# slimarm_apricot-r_b_v1r3.net
KiCad netlist of a schematic drawn in EasyEDA Pro
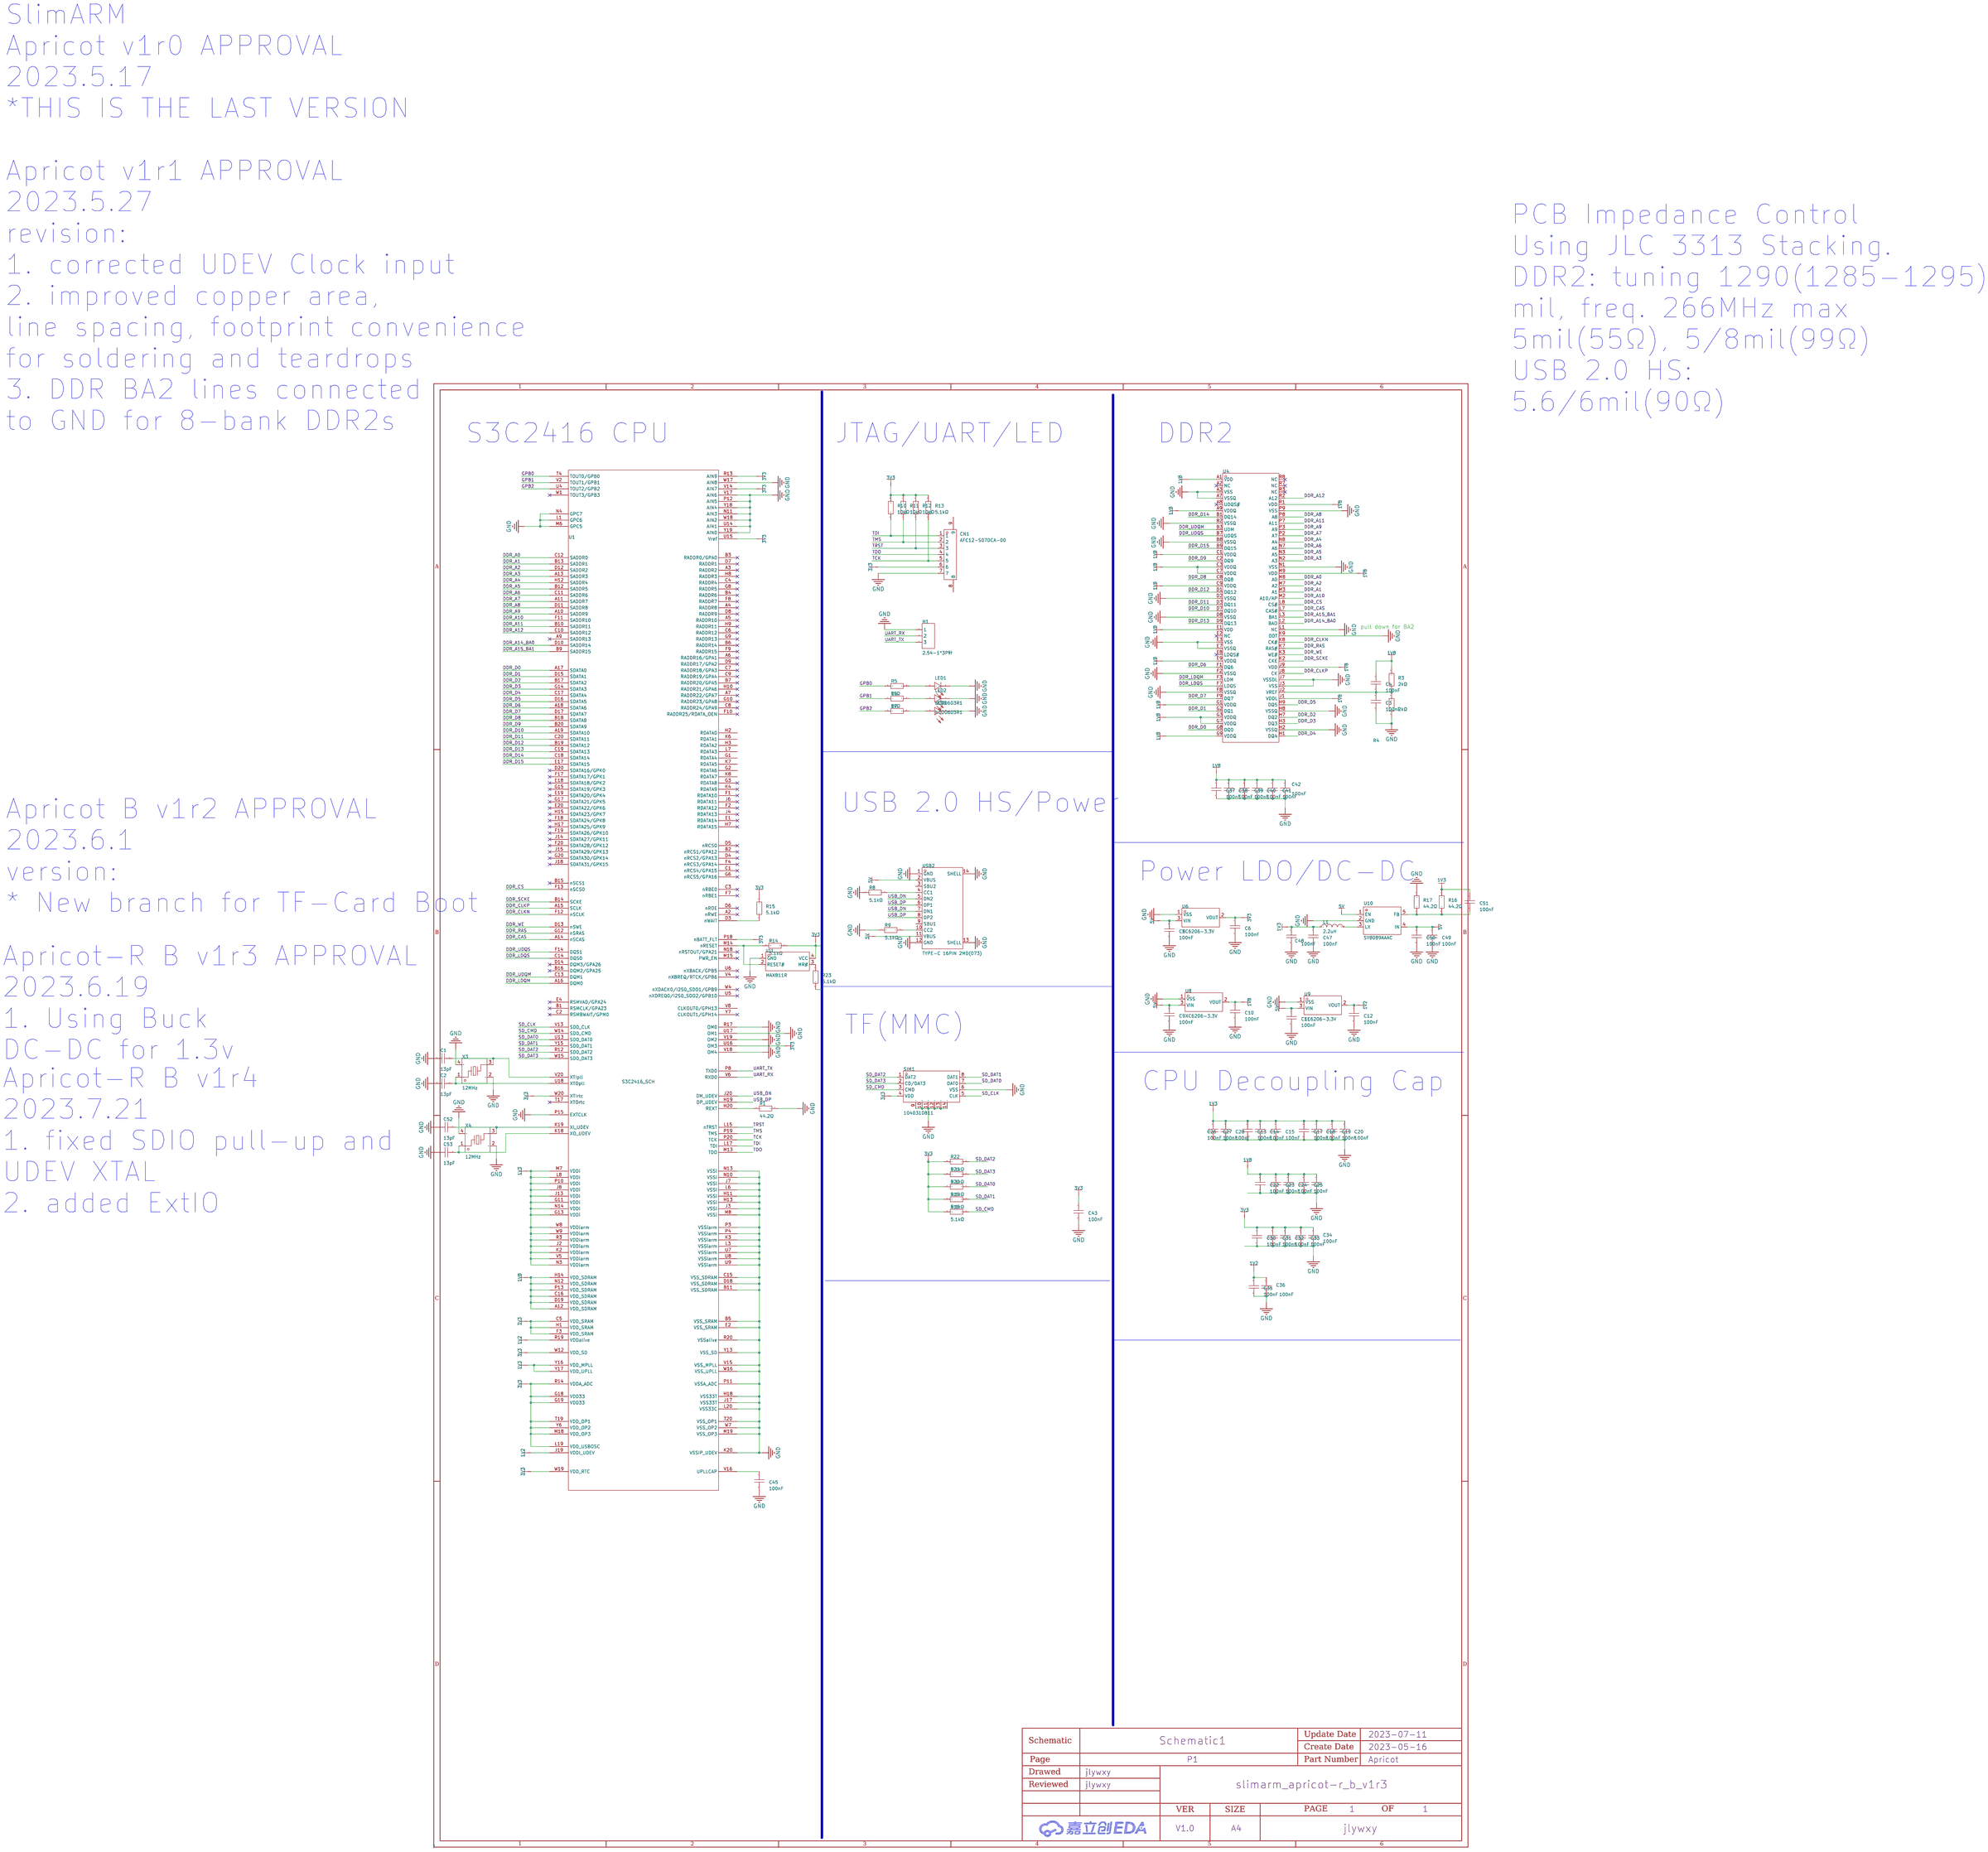
[diagram p0: schematic sheet]

(export (version "E")
  (design (tool "Eeschema 10.0.6"))
  (components
    (comp (ref "C1")
      (value "13pF")
      (footprint "easyedapro:C0402")
      (description "容值:22pF;精度:±5%;额定电压:50V;材质(温度系数):NP0;")
      (fields
        (field (name "Manufacturer Part") "CC0402JRNPO9BN220")
        (field (name "Manufacturer") "YAGEO(国巨)")
      )
      (libsource (lib "easyedapro") (part "CC0402JRNPO9BN220"))
    )
    (comp (ref "C2")
      (value "13pF")
      (footprint "easyedapro:C0402")
      (description "容值:22pF;精度:±5%;额定电压:50V;材质(温度系数):NP0;")
      (fields
        (field (name "Manufacturer Part") "CC0402JRNPO9BN220")
        (field (name "Manufacturer") "YAGEO(国巨)")
      )
      (libsource (lib "easyedapro") (part "CC0402JRNPO9BN220"))
    )
    (comp (ref "C3")
      (value "100nF")
      (footprint "easyedapro:C0402")
      (description "容值:22pF;精度:±5%;额定电压:50V;材质(温度系数):NP0;")
      (fields
        (field (name "Manufacturer Part") "CC0402JRNPO9BN220")
        (field (name "Manufacturer") "YAGEO(国巨)")
      )
      (libsource (lib "easyedapro") (part "CC0402JRNPO9BN220"))
    )
    (comp (ref "C4")
      (value "100nF")
      (footprint "easyedapro:C0402")
      (description "容值:22pF;精度:±5%;额定电压:50V;材质(温度系数):NP0;")
      (fields
        (field (name "Manufacturer Part") "CC0402JRNPO9BN220")
        (field (name "Manufacturer") "YAGEO(国巨)")
      )
      (libsource (lib "easyedapro") (part "CC0402JRNPO9BN220"))
    )
    (comp (ref "C5")
      (value "100nF")
      (footprint "easyedapro:C0402")
      (description "容值:22pF;精度:±5%;额定电压:50V;材质(温度系数):NP0;")
      (fields
        (field (name "Manufacturer Part") "CC0402JRNPO9BN220")
        (field (name "Manufacturer") "YAGEO(国巨)")
      )
      (libsource (lib "easyedapro") (part "CC0402JRNPO9BN220"))
    )
    (comp (ref "C6")
      (value "100nF")
      (footprint "easyedapro:C0402")
      (description "容值:22pF;精度:±5%;额定电压:50V;材质(温度系数):NP0;")
      (fields
        (field (name "Manufacturer Part") "CC0402JRNPO9BN220")
        (field (name "Manufacturer") "YAGEO(国巨)")
      )
      (libsource (lib "easyedapro") (part "CC0402JRNPO9BN220"))
    )
    (comp (ref "C9")
      (value "100nF")
      (footprint "easyedapro:C0402")
      (description "容值:22pF;精度:±5%;额定电压:50V;材质(温度系数):NP0;")
      (fields
        (field (name "Manufacturer Part") "CC0402JRNPO9BN220")
        (field (name "Manufacturer") "YAGEO(国巨)")
      )
      (libsource (lib "easyedapro") (part "CC0402JRNPO9BN220"))
    )
    (comp (ref "C10")
      (value "100nF")
      (footprint "easyedapro:C0402")
      (description "容值:22pF;精度:±5%;额定电压:50V;材质(温度系数):NP0;")
      (fields
        (field (name "Manufacturer Part") "CC0402JRNPO9BN220")
        (field (name "Manufacturer") "YAGEO(国巨)")
      )
      (libsource (lib "easyedapro") (part "CC0402JRNPO9BN220"))
    )
    (comp (ref "C11")
      (value "100nF")
      (footprint "easyedapro:C0402")
      (description "容值:22pF;精度:±5%;额定电压:50V;材质(温度系数):NP0;")
      (fields
        (field (name "Manufacturer Part") "CC0402JRNPO9BN220")
        (field (name "Manufacturer") "YAGEO(国巨)")
      )
      (libsource (lib "easyedapro") (part "CC0402JRNPO9BN220"))
    )
    (comp (ref "C12")
      (value "100nF")
      (footprint "easyedapro:C0402")
      (description "容值:22pF;精度:±5%;额定电压:50V;材质(温度系数):NP0;")
      (fields
        (field (name "Manufacturer Part") "CC0402JRNPO9BN220")
        (field (name "Manufacturer") "YAGEO(国巨)")
      )
      (libsource (lib "easyedapro") (part "CC0402JRNPO9BN220"))
    )
    (comp (ref "C13")
      (value "100nF")
      (footprint "easyedapro:C0402")
      (description "容值:22pF;精度:±5%;额定电压:50V;材质(温度系数):NP0;")
      (fields
        (field (name "Manufacturer Part") "CC0402JRNPO9BN220")
        (field (name "Manufacturer") "YAGEO(国巨)")
      )
      (libsource (lib "easyedapro") (part "CC0402JRNPO9BN220"))
    )
    (comp (ref "C14")
      (value "100nF")
      (footprint "easyedapro:C0402")
      (description "容值:22pF;精度:±5%;额定电压:50V;材质(温度系数):NP0;")
      (fields
        (field (name "Manufacturer Part") "CC0402JRNPO9BN220")
        (field (name "Manufacturer") "YAGEO(国巨)")
      )
      (libsource (lib "easyedapro") (part "CC0402JRNPO9BN220"))
    )
    (comp (ref "C15")
      (value "100nF")
      (footprint "easyedapro:C0402")
      (description "容值:22pF;精度:±5%;额定电压:50V;材质(温度系数):NP0;")
      (fields
        (field (name "Manufacturer Part") "CC0402JRNPO9BN220")
        (field (name "Manufacturer") "YAGEO(国巨)")
      )
      (libsource (lib "easyedapro") (part "CC0402JRNPO9BN220"))
    )
    (comp (ref "C17")
      (value "100nF")
      (footprint "easyedapro:C0402")
      (description "容值:22pF;精度:±5%;额定电压:50V;材质(温度系数):NP0;")
      (fields
        (field (name "Manufacturer Part") "CC0402JRNPO9BN220")
        (field (name "Manufacturer") "YAGEO(国巨)")
      )
      (libsource (lib "easyedapro") (part "CC0402JRNPO9BN220"))
    )
    (comp (ref "C18")
      (value "100nF")
      (footprint "easyedapro:C0402")
      (description "容值:22pF;精度:±5%;额定电压:50V;材质(温度系数):NP0;")
      (fields
        (field (name "Manufacturer Part") "CC0402JRNPO9BN220")
        (field (name "Manufacturer") "YAGEO(国巨)")
      )
      (libsource (lib "easyedapro") (part "CC0402JRNPO9BN220"))
    )
    (comp (ref "C19")
      (value "100nF")
      (footprint "easyedapro:C0402")
      (description "容值:22pF;精度:±5%;额定电压:50V;材质(温度系数):NP0;")
      (fields
        (field (name "Manufacturer Part") "CC0402JRNPO9BN220")
        (field (name "Manufacturer") "YAGEO(国巨)")
      )
      (libsource (lib "easyedapro") (part "CC0402JRNPO9BN220"))
    )
    (comp (ref "C20")
      (value "100nF")
      (footprint "easyedapro:C0402")
      (description "容值:22pF;精度:±5%;额定电压:50V;材质(温度系数):NP0;")
      (fields
        (field (name "Manufacturer Part") "CC0402JRNPO9BN220")
        (field (name "Manufacturer") "YAGEO(国巨)")
      )
      (libsource (lib "easyedapro") (part "CC0402JRNPO9BN220"))
    )
    (comp (ref "C22")
      (value "100nF")
      (footprint "easyedapro:C0402")
      (description "容值:22pF;精度:±5%;额定电压:50V;材质(温度系数):NP0;")
      (fields
        (field (name "Manufacturer Part") "CC0402JRNPO9BN220")
        (field (name "Manufacturer") "YAGEO(国巨)")
      )
      (libsource (lib "easyedapro") (part "CC0402JRNPO9BN220"))
    )
    (comp (ref "C23")
      (value "100nF")
      (footprint "easyedapro:C0402")
      (description "容值:22pF;精度:±5%;额定电压:50V;材质(温度系数):NP0;")
      (fields
        (field (name "Manufacturer Part") "CC0402JRNPO9BN220")
        (field (name "Manufacturer") "YAGEO(国巨)")
      )
      (libsource (lib "easyedapro") (part "CC0402JRNPO9BN220"))
    )
    (comp (ref "C24")
      (value "100nF")
      (footprint "easyedapro:C0402")
      (description "容值:22pF;精度:±5%;额定电压:50V;材质(温度系数):NP0;")
      (fields
        (field (name "Manufacturer Part") "CC0402JRNPO9BN220")
        (field (name "Manufacturer") "YAGEO(国巨)")
      )
      (libsource (lib "easyedapro") (part "CC0402JRNPO9BN220"))
    )
    (comp (ref "C25")
      (value "100nF")
      (footprint "easyedapro:C0402")
      (description "容值:22pF;精度:±5%;额定电压:50V;材质(温度系数):NP0;")
      (fields
        (field (name "Manufacturer Part") "CC0402JRNPO9BN220")
        (field (name "Manufacturer") "YAGEO(国巨)")
      )
      (libsource (lib "easyedapro") (part "CC0402JRNPO9BN220"))
    )
    (comp (ref "C26")
      (value "100nF")
      (footprint "easyedapro:C0402")
      (description "容值:22pF;精度:±5%;额定电压:50V;材质(温度系数):NP0;")
      (fields
        (field (name "Manufacturer Part") "CC0402JRNPO9BN220")
        (field (name "Manufacturer") "YAGEO(国巨)")
      )
      (libsource (lib "easyedapro") (part "CC0402JRNPO9BN220"))
    )
    (comp (ref "C27")
      (value "100nF")
      (footprint "easyedapro:C0402")
      (description "容值:22pF;精度:±5%;额定电压:50V;材质(温度系数):NP0;")
      (fields
        (field (name "Manufacturer Part") "CC0402JRNPO9BN220")
        (field (name "Manufacturer") "YAGEO(国巨)")
      )
      (libsource (lib "easyedapro") (part "CC0402JRNPO9BN220"))
    )
    (comp (ref "C28")
      (value "100nF")
      (footprint "easyedapro:C0402")
      (description "容值:22pF;精度:±5%;额定电压:50V;材质(温度系数):NP0;")
      (fields
        (field (name "Manufacturer Part") "CC0402JRNPO9BN220")
        (field (name "Manufacturer") "YAGEO(国巨)")
      )
      (libsource (lib "easyedapro") (part "CC0402JRNPO9BN220"))
    )
    (comp (ref "C30")
      (value "100nF")
      (footprint "easyedapro:C0402")
      (description "容值:22pF;精度:±5%;额定电压:50V;材质(温度系数):NP0;")
      (fields
        (field (name "Manufacturer Part") "CC0402JRNPO9BN220")
        (field (name "Manufacturer") "YAGEO(国巨)")
      )
      (libsource (lib "easyedapro") (part "CC0402JRNPO9BN220"))
    )
    (comp (ref "C31")
      (value "100nF")
      (footprint "easyedapro:C0402")
      (description "容值:22pF;精度:±5%;额定电压:50V;材质(温度系数):NP0;")
      (fields
        (field (name "Manufacturer Part") "CC0402JRNPO9BN220")
        (field (name "Manufacturer") "YAGEO(国巨)")
      )
      (libsource (lib "easyedapro") (part "CC0402JRNPO9BN220"))
    )
    (comp (ref "C32")
      (value "100nF")
      (footprint "easyedapro:C0402")
      (description "容值:22pF;精度:±5%;额定电压:50V;材质(温度系数):NP0;")
      (fields
        (field (name "Manufacturer Part") "CC0402JRNPO9BN220")
        (field (name "Manufacturer") "YAGEO(国巨)")
      )
      (libsource (lib "easyedapro") (part "CC0402JRNPO9BN220"))
    )
    (comp (ref "C33")
      (value "100nF")
      (footprint "easyedapro:C0402")
      (description "容值:22pF;精度:±5%;额定电压:50V;材质(温度系数):NP0;")
      (fields
        (field (name "Manufacturer Part") "CC0402JRNPO9BN220")
        (field (name "Manufacturer") "YAGEO(国巨)")
      )
      (libsource (lib "easyedapro") (part "CC0402JRNPO9BN220"))
    )
    (comp (ref "C34")
      (value "100nF")
      (footprint "easyedapro:C0402")
      (description "容值:22pF;精度:±5%;额定电压:50V;材质(温度系数):NP0;")
      (fields
        (field (name "Manufacturer Part") "CC0402JRNPO9BN220")
        (field (name "Manufacturer") "YAGEO(国巨)")
      )
      (libsource (lib "easyedapro") (part "CC0402JRNPO9BN220"))
    )
    (comp (ref "C35")
      (value "100nF")
      (footprint "easyedapro:C0402")
      (description "容值:22pF;精度:±5%;额定电压:50V;材质(温度系数):NP0;")
      (fields
        (field (name "Manufacturer Part") "CC0402JRNPO9BN220")
        (field (name "Manufacturer") "YAGEO(国巨)")
      )
      (libsource (lib "easyedapro") (part "CC0402JRNPO9BN220"))
    )
    (comp (ref "C36")
      (value "100nF")
      (footprint "easyedapro:C0402")
      (description "容值:22pF;精度:±5%;额定电压:50V;材质(温度系数):NP0;")
      (fields
        (field (name "Manufacturer Part") "CC0402JRNPO9BN220")
        (field (name "Manufacturer") "YAGEO(国巨)")
      )
      (libsource (lib "easyedapro") (part "CC0402JRNPO9BN220"))
    )
    (comp (ref "C37")
      (value "100nF")
      (footprint "easyedapro:C0402")
      (description "容值:22pF;精度:±5%;额定电压:50V;材质(温度系数):NP0;")
      (fields
        (field (name "Manufacturer Part") "CC0402JRNPO9BN220")
        (field (name "Manufacturer") "YAGEO(国巨)")
      )
      (libsource (lib "easyedapro") (part "CC0402JRNPO9BN220"))
    )
    (comp (ref "C38")
      (value "100nF")
      (footprint "easyedapro:C0402")
      (description "容值:22pF;精度:±5%;额定电压:50V;材质(温度系数):NP0;")
      (fields
        (field (name "Manufacturer Part") "CC0402JRNPO9BN220")
        (field (name "Manufacturer") "YAGEO(国巨)")
      )
      (libsource (lib "easyedapro") (part "CC0402JRNPO9BN220"))
    )
    (comp (ref "C39")
      (value "100nF")
      (footprint "easyedapro:C0402")
      (description "容值:22pF;精度:±5%;额定电压:50V;材质(温度系数):NP0;")
      (fields
        (field (name "Manufacturer Part") "CC0402JRNPO9BN220")
        (field (name "Manufacturer") "YAGEO(国巨)")
      )
      (libsource (lib "easyedapro") (part "CC0402JRNPO9BN220"))
    )
    (comp (ref "C40")
      (value "100nF")
      (footprint "easyedapro:C0402")
      (description "容值:22pF;精度:±5%;额定电压:50V;材质(温度系数):NP0;")
      (fields
        (field (name "Manufacturer Part") "CC0402JRNPO9BN220")
        (field (name "Manufacturer") "YAGEO(国巨)")
      )
      (libsource (lib "easyedapro") (part "CC0402JRNPO9BN220"))
    )
    (comp (ref "C41")
      (value "100nF")
      (footprint "easyedapro:C0402")
      (description "容值:22pF;精度:±5%;额定电压:50V;材质(温度系数):NP0;")
      (fields
        (field (name "Manufacturer Part") "CC0402JRNPO9BN220")
        (field (name "Manufacturer") "YAGEO(国巨)")
      )
      (libsource (lib "easyedapro") (part "CC0402JRNPO9BN220"))
    )
    (comp (ref "C42")
      (value "100nF")
      (footprint "easyedapro:C0402")
      (description "容值:22pF;精度:±5%;额定电压:50V;材质(温度系数):NP0;")
      (fields
        (field (name "Manufacturer Part") "CC0402JRNPO9BN220")
        (field (name "Manufacturer") "YAGEO(国巨)")
      )
      (libsource (lib "easyedapro") (part "CC0402JRNPO9BN220"))
    )
    (comp (ref "C43")
      (value "100nF")
      (footprint "easyedapro:C0402")
      (description "容值:22pF;精度:±5%;额定电压:50V;材质(温度系数):NP0;")
      (fields
        (field (name "Manufacturer Part") "CC0402JRNPO9BN220")
        (field (name "Manufacturer") "YAGEO(国巨)")
      )
      (libsource (lib "easyedapro") (part "CC0402JRNPO9BN220"))
    )
    (comp (ref "C45")
      (value "100nF")
      (footprint "easyedapro:C0402")
      (description "容值:22pF;精度:±5%;额定电压:50V;材质(温度系数):NP0;")
      (fields
        (field (name "Manufacturer Part") "CC0402JRNPO9BN220")
        (field (name "Manufacturer") "YAGEO(国巨)")
      )
      (libsource (lib "easyedapro") (part "CC0402JRNPO9BN220"))
    )
    (comp (ref "C47")
      (value "100nF")
      (footprint "easyedapro:C0402")
      (description "容值:22pF;精度:±5%;额定电压:50V;材质(温度系数):NP0;")
      (fields
        (field (name "Manufacturer Part") "CC0402JRNPO9BN220")
        (field (name "Manufacturer") "YAGEO(国巨)")
      )
      (libsource (lib "easyedapro") (part "CC0402JRNPO9BN220"))
    )
    (comp (ref "C48")
      (value "100nF")
      (footprint "easyedapro:C0402")
      (description "容值:22pF;精度:±5%;额定电压:50V;材质(温度系数):NP0;")
      (fields
        (field (name "Manufacturer Part") "CC0402JRNPO9BN220")
        (field (name "Manufacturer") "YAGEO(国巨)")
      )
      (libsource (lib "easyedapro") (part "CC0402JRNPO9BN220"))
    )
    (comp (ref "C49")
      (value "100nF")
      (footprint "easyedapro:C0402")
      (description "容值:22pF;精度:±5%;额定电压:50V;材质(温度系数):NP0;")
      (fields
        (field (name "Manufacturer Part") "CC0402JRNPO9BN220")
        (field (name "Manufacturer") "YAGEO(国巨)")
      )
      (libsource (lib "easyedapro") (part "CC0402JRNPO9BN220"))
    )
    (comp (ref "C50")
      (value "100nF")
      (footprint "easyedapro:C0402")
      (description "容值:22pF;精度:±5%;额定电压:50V;材质(温度系数):NP0;")
      (fields
        (field (name "Manufacturer Part") "CC0402JRNPO9BN220")
        (field (name "Manufacturer") "YAGEO(国巨)")
      )
      (libsource (lib "easyedapro") (part "CC0402JRNPO9BN220"))
    )
    (comp (ref "C51")
      (value "100nF")
      (footprint "easyedapro:C0402")
      (description "容值:22pF;精度:±5%;额定电压:50V;材质(温度系数):NP0;")
      (fields
        (field (name "Manufacturer Part") "CC0402JRNPO9BN220")
        (field (name "Manufacturer") "YAGEO(国巨)")
      )
      (libsource (lib "easyedapro") (part "CC0402JRNPO9BN220"))
    )
    (comp (ref "C52")
      (value "13pF")
      (footprint "easyedapro:C0402")
      (description "容值:22pF;精度:±5%;额定电压:50V;材质(温度系数):NP0;")
      (fields
        (field (name "Manufacturer Part") "CC0402JRNPO9BN220")
        (field (name "Manufacturer") "YAGEO(国巨)")
      )
      (libsource (lib "easyedapro") (part "CC0402JRNPO9BN220"))
    )
    (comp (ref "C53")
      (value "13pF")
      (footprint "easyedapro:C0402")
      (description "容值:22pF;精度:±5%;额定电压:50V;材质(温度系数):NP0;")
      (fields
        (field (name "Manufacturer Part") "CC0402JRNPO9BN220")
        (field (name "Manufacturer") "YAGEO(国巨)")
      )
      (libsource (lib "easyedapro") (part "CC0402JRNPO9BN220"))
    )
    (comp (ref "CN1")
      (value "AFC12-S07DCA-00")
      (footprint "easyedapro:CONN-SMD_AFC12-S07DCA-00")
      (description "参考系列:-;间距:1.25mm;插针结构:1x7P;排数:1;每排PIN数:7;行距:-;公母:公型插针;安装方式:卧贴;额定电流:1A;工作温度范围:-20°C~+85°C;")
      (fields (field (name "Manufacturer") "JS(钜硕电子)"))
      (libsource (lib "easyedapro") (part "AFC12-S07DCA-00"))
    )
    (comp (ref "H1")
      (value "2.54-1*3P针")
      (footprint "easyedapro:HDR-TH_3P-P2.54-V-M-1")
      (fields (field (name "Manufacturer") "BOOMELE(博穆精密)"))
      (libsource (lib "easyedapro") (part "Header-Male-2.54_1x3"))
    )
    (comp (ref "L1")
      (value "2.2uH")
      (footprint "easyedapro:IND-SMD_L3.0-W3.0")
      (description "电感值:2.2uH;精度:±20%;额定电流:2A;")
      (fields (field (name "Manufacturer Part") "SWPA3015S2R2MT") (field (name "Manufacturer") "Sunlord(顺络)"))
      (libsource (lib "easyedapro") (part "SWPA3015S2R2MT"))
    )
    (comp (ref "LED1")
      (value "NCD0603R1")
      (footprint "easyedapro:LED0603-RD_RED")
      (description "发光颜色:红灯;")
      (fields (field (name "Manufacturer") "国星光电"))
      (libsource (lib "easyedapro") (part "FC-DA1608HRK-620D"))
    )
    (comp (ref "LED2")
      (value "NCD0603R1")
      (footprint "easyedapro:LED0603-RD_RED")
      (description "发光颜色:红灯;")
      (fields (field (name "Manufacturer") "国星光电"))
      (libsource (lib "easyedapro") (part "FC-DA1608HRK-620D"))
    )
    (comp (ref "LED3")
      (value "NCD0603R1")
      (footprint "easyedapro:LED0603-RD_RED")
      (description "发光颜色:红灯;")
      (fields (field (name "Manufacturer") "国星光电"))
      (libsource (lib "easyedapro") (part "FC-DA1608HRK-620D"))
    )
    (comp (ref "R1")
      (value "44.2Ω")
      (footprint "easyedapro:R0402")
      (description "阻值:44.2Ω;精度:±1%;功率:62.5mW;")
      (fields (field (name "Manufacturer Part") "RCT0244R2FLF") (field (name "Manufacturer") "HKR"))
      (libsource (lib "easyedapro") (part "RCT0244R2FLF"))
    )
    (comp (ref "R3")
      (value "2kΩ")
      (footprint "easyedapro:R0402")
      (description "阻值:44.2Ω;精度:±1%;功率:62.5mW;")
      (fields (field (name "Manufacturer Part") "RCT0244R2FLF") (field (name "Manufacturer") "HKR"))
      (libsource (lib "easyedapro") (part "RCT0244R2FLF"))
    )
    (comp (ref "R4")
      (value "2kΩ")
      (footprint "easyedapro:R0402")
      (description "阻值:44.2Ω;精度:±1%;功率:62.5mW;")
      (fields (field (name "Manufacturer Part") "RCT0244R2FLF") (field (name "Manufacturer") "HKR"))
      (libsource (lib "easyedapro") (part "RCT0244R2FLF"))
    )
    (comp (ref "R5")
      (value "1kΩ")
      (footprint "easyedapro:R0603")
      (description "电阻类型:厚膜电阻;阻值:1kΩ;精度:±1%;功率:100mW;")
      (fields
        (field (name "Manufacturer Part") "0603WAF1001T5E")
        (field (name "Manufacturer") "UNI-ROYAL(厚声)")
      )
      (libsource (lib "easyedapro") (part "0603WAF1001T5E"))
    )
    (comp (ref "R6")
      (value "1kΩ")
      (footprint "easyedapro:R0603")
      (description "电阻类型:厚膜电阻;阻值:1kΩ;精度:±1%;功率:100mW;")
      (fields
        (field (name "Manufacturer Part") "0603WAF1001T5E")
        (field (name "Manufacturer") "UNI-ROYAL(厚声)")
      )
      (libsource (lib "easyedapro") (part "0603WAF1001T5E"))
    )
    (comp (ref "R7")
      (value "1kΩ")
      (footprint "easyedapro:R0603")
      (description "电阻类型:厚膜电阻;阻值:1kΩ;精度:±1%;功率:100mW;")
      (fields
        (field (name "Manufacturer Part") "0603WAF1001T5E")
        (field (name "Manufacturer") "UNI-ROYAL(厚声)")
      )
      (libsource (lib "easyedapro") (part "0603WAF1001T5E"))
    )
    (comp (ref "R8")
      (value "5.1kΩ")
      (footprint "easyedapro:R0402")
      (description "电阻类型:厚膜电阻;阻值:5.1kΩ;精度:±1%;功率:62.5mW;")
      (fields
        (field (name "Manufacturer Part") "0402WGF5101TCE")
        (field (name "Manufacturer") "UNI-ROYAL(厚声)")
      )
      (libsource (lib "easyedapro") (part "0402WGF5101TCE"))
    )
    (comp (ref "R9")
      (value "5.1kΩ")
      (footprint "easyedapro:R0402")
      (description "电阻类型:厚膜电阻;阻值:5.1kΩ;精度:±1%;功率:62.5mW;")
      (fields
        (field (name "Manufacturer Part") "0402WGF5101TCE")
        (field (name "Manufacturer") "UNI-ROYAL(厚声)")
      )
      (libsource (lib "easyedapro") (part "0402WGF5101TCE"))
    )
    (comp (ref "R10")
      (value "10kΩ")
      (footprint "easyedapro:R0402")
      (description "电阻类型:厚膜电阻;阻值:5.1kΩ;精度:±1%;功率:62.5mW;")
      (fields
        (field (name "Manufacturer Part") "0402WGF5101TCE")
        (field (name "Manufacturer") "UNI-ROYAL(厚声)")
      )
      (libsource (lib "easyedapro") (part "0402WGF5101TCE"))
    )
    (comp (ref "R11")
      (value "10kΩ")
      (footprint "easyedapro:R0402")
      (description "电阻类型:厚膜电阻;阻值:5.1kΩ;精度:±1%;功率:62.5mW;")
      (fields
        (field (name "Manufacturer Part") "0402WGF5101TCE")
        (field (name "Manufacturer") "UNI-ROYAL(厚声)")
      )
      (libsource (lib "easyedapro") (part "0402WGF5101TCE"))
    )
    (comp (ref "R12")
      (value "10kΩ")
      (footprint "easyedapro:R0402")
      (description "电阻类型:厚膜电阻;阻值:5.1kΩ;精度:±1%;功率:62.5mW;")
      (fields
        (field (name "Manufacturer Part") "0402WGF5101TCE")
        (field (name "Manufacturer") "UNI-ROYAL(厚声)")
      )
      (libsource (lib "easyedapro") (part "0402WGF5101TCE"))
    )
    (comp (ref "R13")
      (value "5.1kΩ")
      (footprint "easyedapro:R0402")
      (description "电阻类型:厚膜电阻;阻值:5.1kΩ;精度:±1%;功率:62.5mW;")
      (fields
        (field (name "Manufacturer Part") "0402WGF5101TCE")
        (field (name "Manufacturer") "UNI-ROYAL(厚声)")
      )
      (libsource (lib "easyedapro") (part "0402WGF5101TCE"))
    )
    (comp (ref "R14")
      (value "5.1kΩ")
      (footprint "easyedapro:R0402")
      (description "电阻类型:厚膜电阻;阻值:5.1kΩ;精度:±1%;功率:62.5mW;")
      (fields
        (field (name "Manufacturer Part") "0402WGF5101TCE")
        (field (name "Manufacturer") "UNI-ROYAL(厚声)")
      )
      (libsource (lib "easyedapro") (part "0402WGF5101TCE"))
    )
    (comp (ref "R15")
      (value "5.1kΩ")
      (footprint "easyedapro:R0402")
      (description "电阻类型:厚膜电阻;阻值:5.1kΩ;精度:±1%;功率:62.5mW;")
      (fields
        (field (name "Manufacturer Part") "0402WGF5101TCE")
        (field (name "Manufacturer") "UNI-ROYAL(厚声)")
      )
      (libsource (lib "easyedapro") (part "0402WGF5101TCE"))
    )
    (comp (ref "R16")
      (value "44.2Ω")
      (footprint "easyedapro:R0402")
      (description "阻值:44.2Ω;精度:±1%;功率:62.5mW;")
      (fields (field (name "Manufacturer Part") "RCT0244R2FLF") (field (name "Manufacturer") "HKR"))
      (libsource (lib "easyedapro") (part "RCT0244R2FLF"))
    )
    (comp (ref "R17")
      (value "44.2Ω")
      (footprint "easyedapro:R0402")
      (description "阻值:44.2Ω;精度:±1%;功率:62.5mW;")
      (fields (field (name "Manufacturer Part") "RCT0244R2FLF") (field (name "Manufacturer") "HKR"))
      (libsource (lib "easyedapro") (part "RCT0244R2FLF"))
    )
    (comp (ref "R18")
      (value "5.1kΩ")
      (footprint "easyedapro:R0402")
      (description "电阻类型:厚膜电阻;阻值:5.1kΩ;精度:±1%;功率:62.5mW;")
      (fields
        (field (name "Manufacturer Part") "0402WGF5101TCE")
        (field (name "Manufacturer") "UNI-ROYAL(厚声)")
      )
      (libsource (lib "easyedapro") (part "0402WGF5101TCE"))
    )
    (comp (ref "R19")
      (value "5.1kΩ")
      (footprint "easyedapro:R0402")
      (description "电阻类型:厚膜电阻;阻值:5.1kΩ;精度:±1%;功率:62.5mW;")
      (fields
        (field (name "Manufacturer Part") "0402WGF5101TCE")
        (field (name "Manufacturer") "UNI-ROYAL(厚声)")
      )
      (libsource (lib "easyedapro") (part "0402WGF5101TCE"))
    )
    (comp (ref "R20")
      (value "5.1kΩ")
      (footprint "easyedapro:R0402")
      (description "电阻类型:厚膜电阻;阻值:5.1kΩ;精度:±1%;功率:62.5mW;")
      (fields
        (field (name "Manufacturer Part") "0402WGF5101TCE")
        (field (name "Manufacturer") "UNI-ROYAL(厚声)")
      )
      (libsource (lib "easyedapro") (part "0402WGF5101TCE"))
    )
    (comp (ref "R21")
      (value "5.1kΩ")
      (footprint "easyedapro:R0402")
      (description "电阻类型:厚膜电阻;阻值:5.1kΩ;精度:±1%;功率:62.5mW;")
      (fields
        (field (name "Manufacturer Part") "0402WGF5101TCE")
        (field (name "Manufacturer") "UNI-ROYAL(厚声)")
      )
      (libsource (lib "easyedapro") (part "0402WGF5101TCE"))
    )
    (comp (ref "R22")
      (value "5.1kΩ")
      (footprint "easyedapro:R0402")
      (description "电阻类型:厚膜电阻;阻值:5.1kΩ;精度:±1%;功率:62.5mW;")
      (fields
        (field (name "Manufacturer Part") "0402WGF5101TCE")
        (field (name "Manufacturer") "UNI-ROYAL(厚声)")
      )
      (libsource (lib "easyedapro") (part "0402WGF5101TCE"))
    )
    (comp (ref "R23")
      (value "5.1kΩ")
      (footprint "easyedapro:R0402")
      (description "电阻类型:厚膜电阻;阻值:5.1kΩ;精度:±1%;功率:62.5mW;")
      (fields
        (field (name "Manufacturer Part") "0402WGF5101TCE")
        (field (name "Manufacturer") "UNI-ROYAL(厚声)")
      )
      (libsource (lib "easyedapro") (part "0402WGF5101TCE"))
    )
    (comp (ref "SIM1")
      (value "1040310811")
      (footprint "easyedapro:SIM-SMD_8P-1040310811")
      (description "卡连接方式:拔插式;卡类型:MicroSD卡(TF卡);连接器类型:卡座;本体最大高度:1.42mm;触头镀层:金;工作温度范围:-;")
      (fields (field (name "Manufacturer") "MOLEX"))
      (libsource (lib "easyedapro") (part "1040310811"))
    )
    (comp (ref "U1") (value "S3C2416_SCH") (libsource (lib "easyedapro") (part "S3C2416_SCH")))
    (comp (ref "U4")
      (value "NT5TU32M16FG-AC")
      (footprint "easyedapro:VFBGA-84_L7.5-W12.2-P0.80-TL_NANYA_NT5TU32M16FG")
      (fields (field (name "Manufacturer") "Nanya(南亚科技)"))
      (libsource (lib "easyedapro") (part "NT5TU32M16FG-AC"))
    )
    (comp (ref "U6")
      (value "XC6206-3.3V")
      (footprint "easyedapro:SSOT-3_L2.9-W1.6-P0.95-LS2.8-BR")
      (description "输出类型:固定;输出极性:正;最大输入电压:6V;输出电压:3.3V;输出电流:250mA;")
      (fields (field (name "Manufacturer") "YONGYUTAI(永裕泰)"))
      (libsource (lib "easyedapro") (part "XC6206-3.3V"))
    )
    (comp (ref "U8")
      (value "XC6206-3.3V")
      (footprint "easyedapro:SSOT-3_L2.9-W1.6-P0.95-LS2.8-BR")
      (description "输出类型:固定;输出极性:正;最大输入电压:6V;输出电压:3.3V;输出电流:250mA;")
      (fields (field (name "Manufacturer") "YONGYUTAI(永裕泰)"))
      (libsource (lib "easyedapro") (part "XC6206-3.3V"))
    )
    (comp (ref "U9")
      (value "XC6206-3.3V")
      (footprint "easyedapro:SSOT-3_L2.9-W1.6-P0.95-LS2.8-BR")
      (description "输出类型:固定;输出极性:正;最大输入电压:6V;输出电压:3.3V;输出电流:250mA;")
      (fields (field (name "Manufacturer") "YONGYUTAI(永裕泰)"))
      (libsource (lib "easyedapro") (part "XC6206-3.3V"))
    )
    (comp (ref "U10")
      (value "SY8089AAAC")
      (footprint "easyedapro:SOT-23-5_L3.0-W1.7-P0.95-LS2.8-BR")
      (description "功能类型:降压型;同步整流:-;输出通道数:-;拓扑结构:-;输入电压:-;输出电流(最大值):-;开关频率:-;")
      (fields (field (name "Manufacturer") "silergy(矽力杰)"))
      (libsource (lib "easyedapro") (part "SY8089AAAC"))
    )
    (comp (ref "U11")
      (value "MAX811R")
      (footprint "easyedapro:SOT-143R_L2.9-W1.3-P1.92-LS2.3-BL")
      (description "VCC：6V复位电压2.63V容差2.5%")
      (fields (field (name "Manufacturer") "MSKSEMI(美森科)"))
      (libsource (lib "easyedapro") (part "MAX811R"))
    )
    (comp (ref "USB2")
      (value "TYPE-C 16PIN 2MD(073)")
      (footprint "easyedapro:USB-C-SMD_TYPE-C-6PIN-2MD-073")
      (description "连接器类型:Type-C;标准:-;公母:母座;触点数量:16;端口数量:1;安装方式:卧贴;额定电流 - 电源:5A;工作温度范围:-25°C~+85°C;")
      (fields (field (name "Manufacturer") "SHOU HAN(首韩)"))
      (libsource (lib "easyedapro") (part "TYPE-C 16PIN 2MD(073)"))
    )
    (comp (ref "X3")
      (value "12MHz")
      (footprint "easyedapro:CRYSTAL-SMD_4P-L3.2-W2.5-BL")
      (description "频率:12MHz;频率公差:±15ppm;频率稳定度:±25ppm;负载电容:8pF;")
      (fields
        (field (name "Manufacturer Part") "NX3225SA-12MHz-STD-CSR-6")
        (field (name "Manufacturer") "NDK")
      )
      (libsource (lib "easyedapro") (part "NX3225SA-12MHZ-STD-CSR-6"))
    )
    (comp (ref "X4")
      (value "12MHz")
      (footprint "easyedapro:CRYSTAL-SMD_4P-L3.2-W2.5-BL")
      (description "频率:12MHz;频率公差:±15ppm;频率稳定度:±25ppm;负载电容:8pF;")
      (fields
        (field (name "Manufacturer Part") "NX3225SA-12MHz-STD-CSR-6")
        (field (name "Manufacturer") "NDK")
      )
      (libsource (lib "easyedapro") (part "NX3225SA-12MHZ-STD-CSR-6"))
    )
  )
  (nets
    (net (code "1") (name "/DDR_A0") (class "Default")
      (node (ref "U1") (pin "C12") (pinfunction "SADDR0_C12") (pintype "input"))
      (node (ref "U4") (pin "M8") (pinfunction "A0_M8") (pintype "input"))
    )
    (net (code "2") (name "/DDR_A1") (class "Default")
      (node (ref "U1") (pin "B13") (pinfunction "SADDR1_B13") (pintype "input"))
      (node (ref "U4") (pin "M3") (pinfunction "A1_M3") (pintype "input"))
    )
    (net (code "3") (name "/DDR_A2") (class "Default")
      (node (ref "U1") (pin "D12") (pinfunction "SADDR2_D12") (pintype "input"))
      (node (ref "U4") (pin "M7") (pinfunction "A2_M7") (pintype "input"))
    )
    (net (code "4") (name "/DDR_A3") (class "Default")
      (node (ref "U1") (pin "A13") (pinfunction "SADDR3_A13") (pintype "input"))
      (node (ref "U4") (pin "N2") (pinfunction "A3_N2") (pintype "input"))
    )
    (net (code "5") (name "/DDR_A4") (class "Default")
      (node (ref "U1") (pin "H12") (pinfunction "SADDR4_H12") (pintype "input"))
      (node (ref "U4") (pin "N8") (pinfunction "A4_N8") (pintype "input"))
    )
    (net (code "6") (name "/DDR_A5") (class "Default")
      (node (ref "U1") (pin "B12") (pinfunction "SADDR5_B12") (pintype "input"))
      (node (ref "U4") (pin "N3") (pinfunction "A5_N3") (pintype "input"))
    )
    (net (code "7") (name "/DDR_A6") (class "Default")
      (node (ref "U1") (pin "C11") (pinfunction "SADDR6_C11") (pintype "input"))
      (node (ref "U4") (pin "N7") (pinfunction "A6_N7") (pintype "input"))
    )
    (net (code "8") (name "/DDR_A7") (class "Default")
      (node (ref "U1") (pin "A11") (pinfunction "SADDR7_A11") (pintype "input"))
      (node (ref "U4") (pin "P2") (pinfunction "A7_P2") (pintype "input"))
    )
    (net (code "9") (name "/DDR_A8") (class "Default")
      (node (ref "U1") (pin "D11") (pinfunction "SADDR8_D11") (pintype "input"))
      (node (ref "U4") (pin "P8") (pinfunction "A8_P8") (pintype "input"))
    )
    (net (code "10") (name "/DDR_A9") (class "Default")
      (node (ref "U1") (pin "A10") (pinfunction "SADDR9_A10") (pintype "input"))
      (node (ref "U4") (pin "P3") (pinfunction "A9_P3") (pintype "input"))
    )
    (net (code "11") (name "/DDR_A10") (class "Default")
      (node (ref "U1") (pin "F11") (pinfunction "SADDR10_F11") (pintype "input"))
      (node (ref "U4") (pin "M2") (pinfunction "A10/AP_M2") (pintype "input"))
    )
    (net (code "12") (name "/DDR_A11") (class "Default")
      (node (ref "U1") (pin "B10") (pinfunction "SADDR11_B10") (pintype "input"))
      (node (ref "U4") (pin "P7") (pinfunction "A11_P7") (pintype "input"))
    )
    (net (code "13") (name "/DDR_A12") (class "Default")
      (node (ref "U1") (pin "C10") (pinfunction "SADDR12_C10") (pintype "input"))
      (node (ref "U4") (pin "R2") (pinfunction "A12_R2") (pintype "input"))
    )
    (net (code "14") (name "/DDR_A14_BA0") (class "Default")
      (node (ref "U1") (pin "D10") (pinfunction "SADDR14_D10") (pintype "input"))
      (node (ref "U4") (pin "L2") (pinfunction "BAO_L2") (pintype "input"))
    )
    (net (code "15") (name "/DDR_A15_BA1") (class "Default")
      (node (ref "U1") (pin "B9") (pinfunction "SADDR15_B9") (pintype "input"))
      (node (ref "U4") (pin "L3") (pinfunction "BA1_L3") (pintype "input"))
    )
    (net (code "16") (name "/DDR_CAS") (class "Default")
      (node (ref "U1") (pin "A14") (pinfunction "nSCAS_A14") (pintype "input"))
      (node (ref "U4") (pin "L7") (pinfunction "CAS#_L7") (pintype "input"))
    )
    (net (code "17") (name "/DDR_CLKN") (class "Default")
      (node (ref "U1") (pin "F12") (pinfunction "nSCLK_F12") (pintype "input"))
      (node (ref "U4") (pin "K8") (pinfunction "CK#_K8") (pintype "input"))
    )
    (net (code "18") (name "/DDR_CLKP") (class "Default")
      (node (ref "U1") (pin "A15") (pinfunction "SCLK_A15") (pintype "input"))
      (node (ref "U4") (pin "J8") (pinfunction "CK_J8") (pintype "input"))
    )
    (net (code "19") (name "/DDR_CS") (class "Default")
      (node (ref "U1") (pin "F13") (pinfunction "nSCS0_F13") (pintype "input"))
      (node (ref "U4") (pin "L8") (pinfunction "CS#_L8") (pintype "input"))
    )
    (net (code "20") (name "/DDR_D0") (class "Default")
      (node (ref "U1") (pin "A17") (pinfunction "SDATA0_A17") (pintype "input"))
      (node (ref "U4") (pin "G8") (pinfunction "DQ0_G8") (pintype "input"))
    )
    (net (code "21") (name "/DDR_D1") (class "Default")
      (node (ref "U1") (pin "D15") (pinfunction "SDATA1_D15") (pintype "input"))
      (node (ref "U4") (pin "G2") (pinfunction "DQ1_G2") (pintype "input"))
    )
    (net (code "22") (name "/DDR_D2") (class "Default")
      (node (ref "U1") (pin "B17") (pinfunction "SDATA2_B17") (pintype "input"))
      (node (ref "U4") (pin "H7") (pinfunction "DQ2_H7") (pintype "input"))
    )
    (net (code "23") (name "/DDR_D3") (class "Default")
      (node (ref "U1") (pin "G14") (pinfunction "SDATA3_G14") (pintype "input"))
      (node (ref "U4") (pin "H3") (pinfunction "DQ3_H3") (pintype "input"))
    )
    (net (code "24") (name "/DDR_D4") (class "Default")
      (node (ref "U1") (pin "C17") (pinfunction "SDATA4_C17") (pintype "input"))
      (node (ref "U4") (pin "H1") (pinfunction "DQ4_H1") (pintype "input"))
    )
    (net (code "25") (name "/DDR_D5") (class "Default")
      (node (ref "U1") (pin "D16") (pinfunction "SDATA5_D16") (pintype "input"))
      (node (ref "U4") (pin "H9") (pinfunction "DQ5_H9") (pintype "input"))
    )
    (net (code "26") (name "/DDR_D6") (class "Default")
      (node (ref "U1") (pin "A18") (pinfunction "SDATA6_A18") (pintype "input"))
      (node (ref "U4") (pin "F1") (pinfunction "DQ6_F1") (pintype "input"))
    )
    (net (code "27") (name "/DDR_D7") (class "Default")
      (node (ref "U1") (pin "D17") (pinfunction "SDATA7_D17") (pintype "input"))
      (node (ref "U4") (pin "F9") (pinfunction "DQ7_F9") (pintype "input"))
    )
    (net (code "28") (name "/DDR_D8") (class "Default")
      (node (ref "U1") (pin "B18") (pinfunction "SDATA8_B18") (pintype "input"))
      (node (ref "U4") (pin "C8") (pinfunction "DQ8_C8") (pintype "input"))
    )
    (net (code "29") (name "/DDR_D9") (class "Default")
      (node (ref "U1") (pin "B20") (pinfunction "SDATA9_B20") (pintype "input"))
      (node (ref "U4") (pin "C2") (pinfunction "DQ9_C2") (pintype "input"))
    )
    (net (code "30") (name "/DDR_D10") (class "Default")
      (node (ref "U1") (pin "A19") (pinfunction "SDATA10_A19") (pintype "input"))
      (node (ref "U4") (pin "D7") (pinfunction "DQ10_D7") (pintype "input"))
    )
    (net (code "31") (name "/DDR_D11") (class "Default")
      (node (ref "U1") (pin "C20") (pinfunction "SDATA11_C20") (pintype "input"))
      (node (ref "U4") (pin "D3") (pinfunction "DQ11_D3") (pintype "input"))
    )
    (net (code "32") (name "/DDR_D12") (class "Default")
      (node (ref "U1") (pin "B19") (pinfunction "SDATA12_B19") (pintype "input"))
      (node (ref "U4") (pin "D1") (pinfunction "DQ12_D1") (pintype "input"))
    )
    (net (code "33") (name "/DDR_D13") (class "Default")
      (node (ref "U1") (pin "C19") (pinfunction "SDATA13_C19") (pintype "input"))
      (node (ref "U4") (pin "D9") (pinfunction "DQ13_D9") (pintype "input"))
    )
    (net (code "34") (name "/DDR_D14") (class "Default")
      (node (ref "U1") (pin "C18") (pinfunction "SDATA14_C18") (pintype "input"))
      (node (ref "U4") (pin "B1") (pinfunction "DQ14_B1") (pintype "input"))
    )
    (net (code "35") (name "/DDR_D15") (class "Default")
      (node (ref "U1") (pin "E17") (pinfunction "SDATA15_E17") (pintype "input"))
      (node (ref "U4") (pin "B9") (pinfunction "DQ15_B9") (pintype "input"))
    )
    (net (code "36") (name "/DDR_LDQM") (class "Default")
      (node (ref "U1") (pin "A16") (pinfunction "DQM0_A16") (pintype "input"))
      (node (ref "U4") (pin "F3") (pinfunction "LDM_F3") (pintype "input"))
    )
    (net (code "37") (name "/DDR_LDQS") (class "Default")
      (node (ref "U1") (pin "C14") (pinfunction "DQS0_C14") (pintype "input"))
      (node (ref "U4") (pin "F7") (pinfunction "LDQS_F7") (pintype "input"))
    )
    (net (code "38") (name "/DDR_RAS") (class "Default")
      (node (ref "U1") (pin "G12") (pinfunction "nSRAS_G12") (pintype "input"))
      (node (ref "U4") (pin "K7") (pinfunction "RAS#_K7") (pintype "input"))
    )
    (net (code "39") (name "/DDR_SCKE") (class "Default")
      (node (ref "U1") (pin "B14") (pinfunction "SCKE_B14") (pintype "input"))
      (node (ref "U4") (pin "K2") (pinfunction "CKE_K2") (pintype "input"))
    )
    (net (code "40") (name "/DDR_UDQM") (class "Default")
      (node (ref "U1") (pin "C13") (pinfunction "DQM1_C13") (pintype "input"))
      (node (ref "U4") (pin "B3") (pinfunction "UDM_B3") (pintype "input"))
    )
    (net (code "41") (name "/DDR_UDQS") (class "Default")
      (node (ref "U1") (pin "F14") (pinfunction "DQS1_F14") (pintype "input"))
      (node (ref "U4") (pin "B7") (pinfunction "UDQS_B7") (pintype "input"))
    )
    (net (code "42") (name "/DDR_WE") (class "Default")
      (node (ref "U1") (pin "D13") (pinfunction "nSWE_D13") (pintype "input"))
      (node (ref "U4") (pin "K3") (pinfunction "WE#_K3") (pintype "input"))
    )
    (net (code "43") (name "/GPB0") (class "Default")
      (node (ref "R5") (pin "1") (pinfunction "1_1") (pintype "input"))
      (node (ref "U1") (pin "T4") (pinfunction "TOUT0/GPB0_T4") (pintype "input"))
    )
    (net (code "44") (name "/GPB1") (class "Default")
      (node (ref "R6") (pin "1") (pinfunction "1_1") (pintype "input"))
      (node (ref "U1") (pin "V2") (pinfunction "TOUT1/GPB1_V2") (pintype "input"))
    )
    (net (code "45") (name "/GPB2") (class "Default")
      (node (ref "R7") (pin "1") (pinfunction "1_1") (pintype "input"))
      (node (ref "U1") (pin "U4") (pinfunction "TOUT2/GPB2_U4") (pintype "input"))
    )
    (net (code "46") (name "/SD_CLK") (class "Default")
      (node (ref "SIM1") (pin "5") (pinfunction "CLK_5") (pintype "input"))
      (node (ref "U1") (pin "V13") (pinfunction "SD0_CLK_V13") (pintype "input"))
    )
    (net (code "47") (name "/SD_CMD") (class "Default")
      (node (ref "R18") (pin "1") (pinfunction "1_1") (pintype "input"))
      (node (ref "SIM1") (pin "3") (pinfunction "CMD_3") (pintype "input"))
      (node (ref "U1") (pin "W14") (pinfunction "SD0_CMD_W14") (pintype "input"))
    )
    (net (code "48") (name "/SD_DAT0") (class "Default")
      (node (ref "R20") (pin "1") (pinfunction "1_1") (pintype "input"))
      (node (ref "SIM1") (pin "7") (pinfunction "DAT0_7") (pintype "input"))
      (node (ref "U1") (pin "U13") (pinfunction "SD0_DAT0_U13") (pintype "input"))
    )
    (net (code "49") (name "/SD_DAT1") (class "Default")
      (node (ref "R19") (pin "1") (pinfunction "1_1") (pintype "input"))
      (node (ref "SIM1") (pin "8") (pinfunction "DAT1_8") (pintype "input"))
      (node (ref "U1") (pin "Y15") (pinfunction "SD0_DAT1_Y15") (pintype "input"))
    )
    (net (code "50") (name "/SD_DAT2") (class "Default")
      (node (ref "R22") (pin "1") (pinfunction "1_1") (pintype "input"))
      (node (ref "SIM1") (pin "1") (pinfunction "DAT2_1") (pintype "input"))
      (node (ref "U1") (pin "R12") (pinfunction "SD0_DAT2_R12") (pintype "input"))
    )
    (net (code "51") (name "/SD_DAT3") (class "Default")
      (node (ref "R21") (pin "1") (pinfunction "1_1") (pintype "input"))
      (node (ref "SIM1") (pin "2") (pinfunction "CD/DAT3_2") (pintype "input"))
      (node (ref "U1") (pin "W15") (pinfunction "SD0_DAT3_W15") (pintype "input"))
    )
    (net (code "52") (name "/TCK") (class "Default")
      (node (ref "CN1") (pin "5") (pinfunction "5_5") (pintype "input"))
      (node (ref "R13") (pin "1") (pinfunction "1_1") (pintype "input"))
      (node (ref "U1") (pin "P20") (pinfunction "TCK_P20") (pintype "input"))
    )
    (net (code "53") (name "/TDI") (class "Default")
      (node (ref "CN1") (pin "1") (pinfunction "1_1") (pintype "input"))
      (node (ref "R10") (pin "1") (pinfunction "1_1") (pintype "input"))
      (node (ref "U1") (pin "L17") (pinfunction "TDI_L17") (pintype "input"))
    )
    (net (code "54") (name "/TDO") (class "Default")
      (node (ref "CN1") (pin "4") (pinfunction "4_4") (pintype "input"))
      (node (ref "U1") (pin "M13") (pinfunction "TDO_M13") (pintype "output"))
    )
    (net (code "55") (name "/TMS") (class "Default")
      (node (ref "CN1") (pin "2") (pinfunction "2_2") (pintype "input"))
      (node (ref "R11") (pin "1") (pinfunction "1_1") (pintype "input"))
      (node (ref "U1") (pin "P19") (pinfunction "TMS_P19") (pintype "input"))
    )
    (net (code "56") (name "/TRST") (class "Default")
      (node (ref "CN1") (pin "3") (pinfunction "3_3") (pintype "input"))
      (node (ref "R12") (pin "1") (pinfunction "1_1") (pintype "input"))
      (node (ref "U1") (pin "L15") (pinfunction "nTRST_L15") (pintype "input"))
    )
    (net (code "57") (name "/UART_RX") (class "Default")
      (node (ref "H1") (pin "2") (pinfunction "2_2") (pintype "input"))
      (node (ref "U1") (pin "V6") (pinfunction "RXD0_V6") (pintype "input"))
    )
    (net (code "58") (name "/UART_TX") (class "Default")
      (node (ref "H1") (pin "3") (pinfunction "3_3") (pintype "input"))
      (node (ref "U1") (pin "P8") (pinfunction "TXD0_P8") (pintype "output"))
    )
    (net (code "59") (name "/USB_DN") (class "Default")
      (node (ref "U1") (pin "J20") (pinfunction "DM_UDEV_J20") (pintype "bidirectional"))
      (node (ref "USB2") (pin "5") (pinfunction "DN2_5") (pintype "input"))
      (node (ref "USB2") (pin "7") (pinfunction "DN1_7") (pintype "input"))
    )
    (net (code "60") (name "/USB_DP") (class "Default")
      (node (ref "U1") (pin "H19") (pinfunction "DP_UDEV_H19") (pintype "bidirectional"))
      (node (ref "USB2") (pin "6") (pinfunction "DP1_6") (pintype "input"))
      (node (ref "USB2") (pin "8") (pinfunction "DP2_8") (pintype "input"))
    )
    (net (code "61") (name "1V2") (class "Default")
      (node (ref "C12") (pin "1") (pinfunction "1_1") (pintype "input"))
      (node (ref "C35") (pin "1") (pinfunction "1_1") (pintype "input"))
      (node (ref "C36") (pin "1") (pinfunction "1_1") (pintype "input"))
      (node (ref "U1") (pin "J19") (pinfunction "VDDI_UDEV_J19") (pintype "input"))
      (node (ref "U1") (pin "R19") (pinfunction "VDDalive_R19") (pintype "input"))
      (node (ref "U9") (pin "2") (pinfunction "VOUT_2") (pintype "input"))
    )
    (net (code "62") (name "1V3") (class "Default")
      (node (ref "C13") (pin "1") (pinfunction "1_1") (pintype "input"))
      (node (ref "C14") (pin "1") (pinfunction "1_1") (pintype "input"))
      (node (ref "C15") (pin "1") (pinfunction "1_1") (pintype "input"))
      (node (ref "C17") (pin "1") (pinfunction "1_1") (pintype "input"))
      (node (ref "C18") (pin "1") (pinfunction "1_1") (pintype "input"))
      (node (ref "C19") (pin "1") (pinfunction "1_1") (pintype "input"))
      (node (ref "C20") (pin "1") (pinfunction "1_1") (pintype "input"))
      (node (ref "C27") (pin "1") (pinfunction "1_1") (pintype "input"))
      (node (ref "C28") (pin "1") (pinfunction "1_1") (pintype "input"))
      (node (ref "C47") (pin "1") (pinfunction "1_1") (pintype "input"))
      (node (ref "C48") (pin "1") (pinfunction "1_1") (pintype "input"))
      (node (ref "C51") (pin "1") (pinfunction "1_1") (pintype "input"))
      (node (ref "L1") (pin "1") (pinfunction "1_1") (pintype "input"))
      (node (ref "R16") (pin "1") (pinfunction "1_1") (pintype "input"))
      (node (ref "U1") (pin "G11") (pinfunction "VDDi_G11") (pintype "input"))
      (node (ref "U1") (pin "G13") (pinfunction "VDDi_G13") (pintype "input"))
      (node (ref "U1") (pin "J13") (pinfunction "VDDi_J13") (pintype "input"))
      (node (ref "U1") (pin "J2") (pinfunction "VDDiarm_J2") (pintype "input"))
      (node (ref "U1") (pin "J8") (pinfunction "VDDi_J8") (pintype "input"))
      (node (ref "U1") (pin "K2") (pinfunction "VDDiarm_K2") (pintype "input"))
      (node (ref "U1") (pin "L8") (pinfunction "VDDi_L8") (pintype "input"))
      (node (ref "U1") (pin "M7") (pinfunction "VDDi_M7") (pintype "input"))
      (node (ref "U1") (pin "N14") (pinfunction "VDDi_N14") (pintype "input"))
      (node (ref "U1") (pin "N3") (pinfunction "VDDiarm_N3") (pintype "input"))
      (node (ref "U1") (pin "P10") (pinfunction "VDDi_P10") (pintype "input"))
      (node (ref "U1") (pin "R3") (pinfunction "VDDiarm_R3") (pintype "input"))
      (node (ref "U1") (pin "V5") (pinfunction "VDDiarm_V5") (pintype "input"))
      (node (ref "U1") (pin "W8") (pinfunction "VDDiarm_W8") (pintype "input"))
      (node (ref "U1") (pin "W9") (pinfunction "VDDiarm_W9") (pintype "input"))
      (node (ref "U1") (pin "Y16") (pinfunction "VDD_MPLL_Y16") (pintype "input"))
      (node (ref "U1") (pin "Y17") (pinfunction "VDD_UPLL_Y17") (pintype "input"))
    )
    (net (code "63") (name "1V8") (class "Default")
      (node (ref "C10") (pin "1") (pinfunction "1_1") (pintype "input"))
      (node (ref "C22") (pin "1") (pinfunction "1_1") (pintype "input"))
      (node (ref "C23") (pin "1") (pinfunction "1_1") (pintype "input"))
      (node (ref "C24") (pin "1") (pinfunction "1_1") (pintype "input"))
      (node (ref "C25") (pin "1") (pinfunction "1_1") (pintype "input"))
      (node (ref "C26") (pin "1") (pinfunction "1_1") (pintype "input"))
      (node (ref "C37") (pin "1") (pinfunction "1_1") (pintype "input"))
      (node (ref "C38") (pin "1") (pinfunction "1_1") (pintype "input"))
      (node (ref "C39") (pin "1") (pinfunction "1_1") (pintype "input"))
      (node (ref "C4") (pin "1") (pinfunction "1_1") (pintype "input"))
      (node (ref "C40") (pin "1") (pinfunction "1_1") (pintype "input"))
      (node (ref "C41") (pin "1") (pinfunction "1_1") (pintype "input"))
      (node (ref "C42") (pin "1") (pinfunction "1_1") (pintype "input"))
      (node (ref "R3") (pin "2") (pinfunction "2_2") (pintype "input"))
      (node (ref "U1") (pin "A12") (pinfunction "VDD_SDRAM_A12") (pintype "input"))
      (node (ref "U1") (pin "C16") (pinfunction "VDD_SDRAM_C16") (pintype "input"))
      (node (ref "U1") (pin "D19") (pinfunction "VDD_SDRAM_D19") (pintype "input"))
      (node (ref "U1") (pin "H14") (pinfunction "VDD_SDRAM_H14") (pintype "input"))
      (node (ref "U1") (pin "N12") (pinfunction "VDD_SDRAM_N12") (pintype "input"))
      (node (ref "U1") (pin "P13") (pinfunction "VDD_SDRAM_P13") (pintype "input"))
      (node (ref "U4") (pin "A1") (pinfunction "VDD_A1") (pintype "input"))
      (node (ref "U4") (pin "A9") (pinfunction "VDDQ_A9") (pintype "input"))
      (node (ref "U4") (pin "C1") (pinfunction "VDDQ_C1") (pintype "input"))
      (node (ref "U4") (pin "C3") (pinfunction "VDDQ_C3") (pintype "input"))
      (node (ref "U4") (pin "C7") (pinfunction "VDDQ_C7") (pintype "input"))
      (node (ref "U4") (pin "C9") (pinfunction "VDDQ_C9") (pintype "input"))
      (node (ref "U4") (pin "E1") (pinfunction "VDD_E1") (pintype "input"))
      (node (ref "U4") (pin "E9") (pinfunction "VDDQ_E9") (pintype "input"))
      (node (ref "U4") (pin "G1") (pinfunction "VDDQ_G1") (pintype "input"))
      (node (ref "U4") (pin "G3") (pinfunction "VDDQ_G3") (pintype "input"))
      (node (ref "U4") (pin "G7") (pinfunction "VDDQ_G7") (pintype "input"))
      (node (ref "U4") (pin "G9") (pinfunction "VDDQ_G9") (pintype "input"))
      (node (ref "U4") (pin "J1") (pinfunction "VDDL_J1") (pintype "input"))
      (node (ref "U4") (pin "J9") (pinfunction "VDD_J9") (pintype "input"))
      (node (ref "U4") (pin "M9") (pinfunction "VDD_M9") (pintype "input"))
      (node (ref "U4") (pin "R1") (pinfunction "VDD_R1") (pintype "input"))
      (node (ref "U8") (pin "2") (pinfunction "VOUT_2") (pintype "input"))
    )
    (net (code "64") (name "3V3") (class "Default")
      (node (ref "C30") (pin "1") (pinfunction "1_1") (pintype "input"))
      (node (ref "C31") (pin "1") (pinfunction "1_1") (pintype "input"))
      (node (ref "C32") (pin "1") (pinfunction "1_1") (pintype "input"))
      (node (ref "C33") (pin "1") (pinfunction "1_1") (pintype "input"))
      (node (ref "C34") (pin "1") (pinfunction "1_1") (pintype "input"))
      (node (ref "C43") (pin "1") (pinfunction "1_1") (pintype "input"))
      (node (ref "C6") (pin "1") (pinfunction "1_1") (pintype "input"))
      (node (ref "CN1") (pin "6") (pinfunction "6_6") (pintype "input"))
      (node (ref "R10") (pin "2") (pinfunction "2_2") (pintype "input"))
      (node (ref "R11") (pin "2") (pinfunction "2_2") (pintype "input"))
      (node (ref "R12") (pin "2") (pinfunction "2_2") (pintype "input"))
      (node (ref "R13") (pin "2") (pinfunction "2_2") (pintype "input"))
      (node (ref "R14") (pin "1") (pinfunction "1_1") (pintype "input"))
      (node (ref "R15") (pin "2") (pinfunction "2_2") (pintype "input"))
      (node (ref "R18") (pin "2") (pinfunction "2_2") (pintype "input"))
      (node (ref "R19") (pin "2") (pinfunction "2_2") (pintype "input"))
      (node (ref "R20") (pin "2") (pinfunction "2_2") (pintype "input"))
      (node (ref "R21") (pin "2") (pinfunction "2_2") (pintype "input"))
      (node (ref "R22") (pin "2") (pinfunction "2_2") (pintype "input"))
      (node (ref "R23") (pin "2") (pinfunction "2_2") (pintype "input"))
      (node (ref "SIM1") (pin "4") (pinfunction "VDD_4") (pintype "input"))
      (node (ref "U1") (pin "C5") (pinfunction "VDD_SRAM_C5") (pintype "input"))
      (node (ref "U1") (pin "F3") (pinfunction "VDD_SRAM_F3") (pintype "input"))
      (node (ref "U1") (pin "G18") (pinfunction "VDD33_G18") (pintype "input"))
      (node (ref "U1") (pin "G19") (pinfunction "VDD33_G19") (pintype "input"))
      (node (ref "U1") (pin "H1") (pinfunction "VDD_SRAM_H1") (pintype "input"))
      (node (ref "U1") (pin "L19") (pinfunction "VDD_USBOSC_L19") (pintype "input"))
      (node (ref "U1") (pin "M18") (pinfunction "VDD_OP3_M18") (pintype "input"))
      (node (ref "U1") (pin "P18") (pinfunction "nBATT_FLT_P18") (pintype "input"))
      (node (ref "U1") (pin "R13") (pinfunction "AIN9_R13") (pintype "input"))
      (node (ref "U1") (pin "R14") (pinfunction "VDDA_ADC_R14") (pintype "input"))
      (node (ref "U1") (pin "T19") (pinfunction "VDD_OP1_T19") (pintype "input"))
      (node (ref "U1") (pin "U15") (pinfunction "Vref_U15") (pintype "input"))
      (node (ref "U1") (pin "U16") (pinfunction "OM3_U16") (pintype "input"))
      (node (ref "U1") (pin "V14") (pinfunction "AIN7_V14") (pintype "input"))
      (node (ref "U1") (pin "W12") (pinfunction "VDD_SD_W12") (pintype "input"))
      (node (ref "U1") (pin "W19") (pinfunction "VDD_RTC_W19") (pintype "input"))
      (node (ref "U1") (pin "W20") (pinfunction "XTIrtc_W20") (pintype "input"))
      (node (ref "U1") (pin "Y6") (pinfunction "VDD_OP2_Y6") (pintype "input"))
      (node (ref "U11") (pin "4") (pinfunction "VCC_4") (pintype "input"))
      (node (ref "U6") (pin "2") (pinfunction "VOUT_2") (pintype "input"))
    )
    (net (code "65") (name "5V") (class "Default")
      (node (ref "C11") (pin "1") (pinfunction "1_1") (pintype "input"))
      (node (ref "C49") (pin "1") (pinfunction "1_1") (pintype "input"))
      (node (ref "C5") (pin "1") (pinfunction "1_1") (pintype "input"))
      (node (ref "C50") (pin "1") (pinfunction "1_1") (pintype "input"))
      (node (ref "C9") (pin "1") (pinfunction "1_1") (pintype "input"))
      (node (ref "U10") (pin "1") (pinfunction "EN_1") (pintype "input"))
      (node (ref "U10") (pin "4") (pinfunction "IN_4") (pintype "input"))
      (node (ref "U6") (pin "3") (pinfunction "VIN_3") (pintype "input"))
      (node (ref "U8") (pin "3") (pinfunction "VIN_3") (pintype "input"))
      (node (ref "U9") (pin "3") (pinfunction "VIN_3") (pintype "input"))
      (node (ref "USB2") (pin "11") (pinfunction "VBUS_11") (pintype "input"))
      (node (ref "USB2") (pin "2") (pinfunction "VBUS_2") (pintype "input"))
    )
    (net (code "66") (name "GND") (class "Default")
      (node (ref "C1") (pin "1") (pinfunction "1_1") (pintype "input"))
      (node (ref "C10") (pin "2") (pinfunction "2_2") (pintype "input"))
      (node (ref "C11") (pin "2") (pinfunction "2_2") (pintype "input"))
      (node (ref "C12") (pin "2") (pinfunction "2_2") (pintype "input"))
      (node (ref "C13") (pin "2") (pinfunction "2_2") (pintype "input"))
      (node (ref "C14") (pin "2") (pinfunction "2_2") (pintype "input"))
      (node (ref "C15") (pin "2") (pinfunction "2_2") (pintype "input"))
      (node (ref "C17") (pin "2") (pinfunction "2_2") (pintype "input"))
      (node (ref "C18") (pin "2") (pinfunction "2_2") (pintype "input"))
      (node (ref "C19") (pin "2") (pinfunction "2_2") (pintype "input"))
      (node (ref "C2") (pin "1") (pinfunction "1_1") (pintype "input"))
      (node (ref "C20") (pin "2") (pinfunction "2_2") (pintype "input"))
      (node (ref "C22") (pin "2") (pinfunction "2_2") (pintype "input"))
      (node (ref "C23") (pin "2") (pinfunction "2_2") (pintype "input"))
      (node (ref "C24") (pin "2") (pinfunction "2_2") (pintype "input"))
      (node (ref "C25") (pin "2") (pinfunction "2_2") (pintype "input"))
      (node (ref "C26") (pin "2") (pinfunction "2_2") (pintype "input"))
      (node (ref "C27") (pin "2") (pinfunction "2_2") (pintype "input"))
      (node (ref "C28") (pin "2") (pinfunction "2_2") (pintype "input"))
      (node (ref "C3") (pin "1") (pinfunction "1_1") (pintype "input"))
      (node (ref "C30") (pin "2") (pinfunction "2_2") (pintype "input"))
      (node (ref "C31") (pin "2") (pinfunction "2_2") (pintype "input"))
      (node (ref "C32") (pin "2") (pinfunction "2_2") (pintype "input"))
      (node (ref "C33") (pin "2") (pinfunction "2_2") (pintype "input"))
      (node (ref "C34") (pin "2") (pinfunction "2_2") (pintype "input"))
      (node (ref "C35") (pin "2") (pinfunction "2_2") (pintype "input"))
      (node (ref "C36") (pin "2") (pinfunction "2_2") (pintype "input"))
      (node (ref "C37") (pin "2") (pinfunction "2_2") (pintype "input"))
      (node (ref "C38") (pin "2") (pinfunction "2_2") (pintype "input"))
      (node (ref "C39") (pin "2") (pinfunction "2_2") (pintype "input"))
      (node (ref "C40") (pin "2") (pinfunction "2_2") (pintype "input"))
      (node (ref "C41") (pin "2") (pinfunction "2_2") (pintype "input"))
      (node (ref "C42") (pin "2") (pinfunction "2_2") (pintype "input"))
      (node (ref "C43") (pin "2") (pinfunction "2_2") (pintype "input"))
      (node (ref "C45") (pin "2") (pinfunction "2_2") (pintype "input"))
      (node (ref "C47") (pin "2") (pinfunction "2_2") (pintype "input"))
      (node (ref "C48") (pin "2") (pinfunction "2_2") (pintype "input"))
      (node (ref "C49") (pin "2") (pinfunction "2_2") (pintype "input"))
      (node (ref "C5") (pin "2") (pinfunction "2_2") (pintype "input"))
      (node (ref "C50") (pin "2") (pinfunction "2_2") (pintype "input"))
      (node (ref "C52") (pin "1") (pinfunction "1_1") (pintype "input"))
      (node (ref "C53") (pin "1") (pinfunction "1_1") (pintype "input"))
      (node (ref "C6") (pin "2") (pinfunction "2_2") (pintype "input"))
      (node (ref "C9") (pin "2") (pinfunction "2_2") (pintype "input"))
      (node (ref "CN1") (pin "7") (pinfunction "7_7") (pintype "input"))
      (node (ref "H1") (pin "1") (pinfunction "1_1") (pintype "input"))
      (node (ref "LED1") (pin "1") (pinfunction "K_1") (pintype "input"))
      (node (ref "LED2") (pin "1") (pinfunction "K_1") (pintype "input"))
      (node (ref "LED3") (pin "1") (pinfunction "K_1") (pintype "input"))
      (node (ref "R1") (pin "2") (pinfunction "2_2") (pintype "input"))
      (node (ref "R17") (pin "2") (pinfunction "2_2") (pintype "input"))
      (node (ref "R4") (pin "1") (pinfunction "1_1") (pintype "input"))
      (node (ref "R8") (pin "1") (pinfunction "1_1") (pintype "input"))
      (node (ref "R9") (pin "1") (pinfunction "1_1") (pintype "input"))
      (node (ref "SIM1") (pin "10") (pinfunction "10_10") (pintype "input"))
      (node (ref "SIM1") (pin "11") (pinfunction "11_11") (pintype "input"))
      (node (ref "SIM1") (pin "12") (pinfunction "12_12") (pintype "input"))
      (node (ref "SIM1") (pin "13") (pinfunction "13_13") (pintype "input"))
      (node (ref "SIM1") (pin "14") (pinfunction "14_14") (pintype "input"))
      (node (ref "SIM1") (pin "6") (pinfunction "VSS_6") (pintype "input"))
      (node (ref "SIM1") (pin "9") (pinfunction "9_9") (pintype "input"))
      (node (ref "U1") (pin "B11") (pinfunction "VSS_SDRAM_B11") (pintype "input"))
      (node (ref "U1") (pin "B5") (pinfunction "VSS_SRAM_B5") (pintype "input"))
      (node (ref "U1") (pin "C15") (pinfunction "VSS_SDRAM_C15") (pintype "input"))
      (node (ref "U1") (pin "D18") (pinfunction "VSS_SDRAM_D18") (pintype "input"))
      (node (ref "U1") (pin "E2") (pinfunction "VSS_SRAM_E2") (pintype "input"))
      (node (ref "U1") (pin "H11") (pinfunction "VSSi_H11") (pintype "input"))
      (node (ref "U1") (pin "H13") (pinfunction "VSSi_H13") (pintype "input"))
      (node (ref "U1") (pin "H18") (pinfunction "VSS33T_H18") (pintype "input"))
      (node (ref "U1") (pin "J17") (pinfunction "VSS33T_J17") (pintype "input"))
      (node (ref "U1") (pin "J3") (pinfunction "VSSi_J3") (pintype "input"))
      (node (ref "U1") (pin "J7") (pinfunction "VSSi_J7") (pintype "input"))
      (node (ref "U1") (pin "K20") (pinfunction "VSSIP_UDEV_K20") (pintype "input"))
      (node (ref "U1") (pin "K3") (pinfunction "VSSiarm_K3") (pintype "input"))
      (node (ref "U1") (pin "L1") (pinfunction "GPC6_L1") (pintype "input"))
      (node (ref "U1") (pin "L20") (pinfunction "VSS33C_L20") (pintype "input"))
      (node (ref "U1") (pin "L3") (pinfunction "VSSiarm_L3") (pintype "input"))
      (node (ref "U1") (pin "L6") (pinfunction "VSSi_L6") (pintype "input"))
      (node (ref "U1") (pin "M19") (pinfunction "VSS_OP3_M19") (pintype "input"))
      (node (ref "U1") (pin "M6") (pinfunction "GPC5_M6") (pintype "input"))
      (node (ref "U1") (pin "M8") (pinfunction "VSSi_M8") (pintype "input"))
      (node (ref "U1") (pin "N10") (pinfunction "VSSi_N10") (pintype "input"))
      (node (ref "U1") (pin "N11") (pinfunction "AIN3_N11") (pintype "input"))
      (node (ref "U1") (pin "N13") (pinfunction "VSSi_N13") (pintype "input"))
      (node (ref "U1") (pin "N4") (pinfunction "GPC7_N4") (pintype "input"))
      (node (ref "U1") (pin "P11") (pinfunction "VSSA_ADC_P11") (pintype "input"))
      (node (ref "U1") (pin "P12") (pinfunction "AIN5_P12") (pintype "input"))
      (node (ref "U1") (pin "P15") (pinfunction "EXTCLK_P15") (pintype "input"))
      (node (ref "U1") (pin "P3") (pinfunction "VSSiarm_P3") (pintype "input"))
      (node (ref "U1") (pin "P4") (pinfunction "VSSiarm_P4") (pintype "input"))
      (node (ref "U1") (pin "R17") (pinfunction "OM0_R17") (pintype "input"))
      (node (ref "U1") (pin "R20") (pinfunction "VSSalive_R20") (pintype "input"))
      (node (ref "U1") (pin "T20") (pinfunction "VSS_OP1_T20") (pintype "input"))
      (node (ref "U1") (pin "U14") (pinfunction "AIN1_U14") (pintype "input"))
      (node (ref "U1") (pin "U17") (pinfunction "OM1_U17") (pintype "input"))
      (node (ref "U1") (pin "U7") (pinfunction "VSSiarm_U7") (pintype "input"))
      (node (ref "U1") (pin "U8") (pinfunction "VSSiarm_U8") (pintype "input"))
      (node (ref "U1") (pin "U9") (pinfunction "VSSiarm_U9") (pintype "input"))
      (node (ref "U1") (pin "V15") (pinfunction "VSS_MPLL_V15") (pintype "input"))
      (node (ref "U1") (pin "V17") (pinfunction "AIN6_V17") (pintype "input"))
      (node (ref "U1") (pin "V18") (pinfunction "OM4_V18") (pintype "input"))
      (node (ref "U1") (pin "V19") (pinfunction "OM2_V19") (pintype "input"))
      (node (ref "U1") (pin "W16") (pinfunction "VSS_UPLL_W16") (pintype "input"))
      (node (ref "U1") (pin "W17") (pinfunction "AIN8_W17") (pintype "input"))
      (node (ref "U1") (pin "W18") (pinfunction "AIN2_W18") (pintype "input"))
      (node (ref "U1") (pin "W7") (pinfunction "VSS_OP2_W7") (pintype "input"))
      (node (ref "U1") (pin "Y13") (pinfunction "VSS_SD_Y13") (pintype "input"))
      (node (ref "U1") (pin "Y18") (pinfunction "AIN4_Y18") (pintype "input"))
      (node (ref "U1") (pin "Y19") (pinfunction "AIN0_Y19") (pintype "input"))
      (node (ref "U10") (pin "2") (pinfunction "GND_2") (pintype "input"))
      (node (ref "U11") (pin "1") (pinfunction "GND_1") (pintype "input"))
      (node (ref "U4") (pin "A3") (pinfunction "VSS_A3") (pintype "input"))
      (node (ref "U4") (pin "A7") (pinfunction "VSSQ_A7") (pintype "input"))
      (node (ref "U4") (pin "B2") (pinfunction "VSSQ_B2") (pintype "input"))
      (node (ref "U4") (pin "B8") (pinfunction "VSSQ_B8") (pintype "input"))
      (node (ref "U4") (pin "D2") (pinfunction "VSSQ_D2") (pintype "input"))
      (node (ref "U4") (pin "D8") (pinfunction "VSSQ_D8") (pintype "input"))
      (node (ref "U4") (pin "E3") (pinfunction "VSS_E3") (pintype "input"))
      (node (ref "U4") (pin "E7") (pinfunction "VSSQ_E7") (pintype "input"))
      (node (ref "U4") (pin "F2") (pinfunction "VSSQ_F2") (pintype "input"))
      (node (ref "U4") (pin "F8") (pinfunction "VSSQ_F8") (pintype "input"))
      (node (ref "U4") (pin "H2") (pinfunction "VSSQ_H2") (pintype "input"))
      (node (ref "U4") (pin "H8") (pinfunction "VSSQ_H8") (pintype "input"))
      (node (ref "U4") (pin "J3") (pinfunction "VSS_J3") (pintype "input"))
      (node (ref "U4") (pin "J7") (pinfunction "VSSDL_J7") (pintype "input"))
      (node (ref "U4") (pin "K9") (pinfunction "ODT_K9") (pintype "input"))
      (node (ref "U4") (pin "L1") (pinfunction "NC_L1") (pintype "input"))
      (node (ref "U4") (pin "N1") (pinfunction "VSS_N1") (pintype "input"))
      (node (ref "U4") (pin "P9") (pinfunction "VSS_P9") (pintype "input"))
      (node (ref "U6") (pin "1") (pinfunction "VSS_1") (pintype "input"))
      (node (ref "U8") (pin "1") (pinfunction "VSS_1") (pintype "input"))
      (node (ref "U9") (pin "1") (pinfunction "VSS_1") (pintype "input"))
      (node (ref "USB2") (pin "1") (pinfunction "GND_1") (pintype "input"))
      (node (ref "USB2") (pin "12") (pinfunction "GND_12") (pintype "input"))
      (node (ref "USB2") (pin "13") (pinfunction "SHELL_13") (pintype "input"))
      (node (ref "USB2") (pin "14") (pinfunction "SHELL_14") (pintype "input"))
      (node (ref "X3") (pin "2") (pinfunction "GND_2") (pintype "input"))
      (node (ref "X3") (pin "4") (pinfunction "GND_4") (pintype "input"))
      (node (ref "X4") (pin "2") (pinfunction "GND_2") (pintype "input"))
      (node (ref "X4") (pin "4") (pinfunction "GND_4") (pintype "input"))
    )
    (net (code "67") (name "Net-(LED1-A)") (class "Default")
      (node (ref "LED1") (pin "2") (pinfunction "A_2") (pintype "input"))
      (node (ref "R5") (pin "2") (pinfunction "2_2") (pintype "input"))
    )
    (net (code "68") (name "Net-(LED2-A)") (class "Default")
      (node (ref "LED2") (pin "2") (pinfunction "A_2") (pintype "input"))
      (node (ref "R6") (pin "2") (pinfunction "2_2") (pintype "input"))
    )
    (net (code "69") (name "Net-(LED3-A)") (class "Default")
      (node (ref "LED3") (pin "2") (pinfunction "A_2") (pintype "input"))
      (node (ref "R7") (pin "2") (pinfunction "2_2") (pintype "input"))
    )
    (net (code "70") (name "Net-(U1-REXT)") (class "Default")
      (node (ref "R1") (pin "1") (pinfunction "1_1") (pintype "input"))
      (node (ref "U1") (pin "H20") (pinfunction "REXT_H20") (pintype "output"))
    )
    (net (code "71") (name "Net-(U1-UPLLCAP)") (class "Default")
      (node (ref "C45") (pin "1") (pinfunction "1_1") (pintype "input"))
      (node (ref "U1") (pin "V16") (pinfunction "UPLLCAP_V16") (pintype "input"))
    )
    (net (code "72") (name "Net-(U1-XI_UDEV)") (class "Default")
      (node (ref "C52") (pin "2") (pinfunction "2_2") (pintype "input"))
      (node (ref "U1") (pin "K19") (pinfunction "XI_UDEV_K19") (pintype "output"))
      (node (ref "X4") (pin "3") (pinfunction "3_3") (pintype "input"))
    )
    (net (code "73") (name "Net-(U1-XO_UDEV)") (class "Default")
      (node (ref "C53") (pin "2") (pinfunction "2_2") (pintype "input"))
      (node (ref "U1") (pin "K18") (pinfunction "XO_UDEV_K18") (pintype "output"))
      (node (ref "X4") (pin "1") (pinfunction "1_1") (pintype "input"))
    )
    (net (code "74") (name "Net-(U1-XTIpll)") (class "Default")
      (node (ref "C1") (pin "2") (pinfunction "2_2") (pintype "input"))
      (node (ref "U1") (pin "V20") (pinfunction "XTIpll_V20") (pintype "input"))
      (node (ref "X3") (pin "3") (pinfunction "3_3") (pintype "input"))
    )
    (net (code "75") (name "Net-(U1-XTOpll)") (class "Default")
      (node (ref "C2") (pin "2") (pinfunction "2_2") (pintype "input"))
      (node (ref "U1") (pin "U18") (pinfunction "XTOpll_U18") (pintype "output"))
      (node (ref "X3") (pin "1") (pinfunction "1_1") (pintype "input"))
    )
    (net (code "76") (name "Net-(U1-nRESET)") (class "Default")
      (node (ref "R14") (pin "2") (pinfunction "2_2") (pintype "input"))
      (node (ref "U1") (pin "M14") (pinfunction "nRESET_M14") (pintype "input"))
      (node (ref "U11") (pin "2") (pinfunction "RESET#_2") (pintype "input"))
    )
    (net (code "77") (name "Net-(U1-nWAIT)") (class "Default")
      (node (ref "R15") (pin "1") (pinfunction "1_1") (pintype "input"))
      (node (ref "U1") (pin "D3") (pinfunction "nWAIT_D3") (pintype "input"))
    )
    (net (code "78") (name "Net-(U4-VREF)") (class "Default")
      (node (ref "C3") (pin "2") (pinfunction "2_2") (pintype "input"))
      (node (ref "C4") (pin "2") (pinfunction "2_2") (pintype "input"))
      (node (ref "R3") (pin "1") (pinfunction "1_1") (pintype "input"))
      (node (ref "R4") (pin "2") (pinfunction "2_2") (pintype "input"))
      (node (ref "U4") (pin "J2") (pinfunction "VREF_J2") (pintype "input"))
    )
    (net (code "79") (name "Net-(U10-FB)") (class "Default")
      (node (ref "C51") (pin "2") (pinfunction "2_2") (pintype "input"))
      (node (ref "R16") (pin "2") (pinfunction "2_2") (pintype "input"))
      (node (ref "R17") (pin "1") (pinfunction "1_1") (pintype "input"))
      (node (ref "U10") (pin "5") (pinfunction "FB_5") (pintype "input"))
    )
    (net (code "80") (name "Net-(U10-LX)") (class "Default")
      (node (ref "L1") (pin "2") (pinfunction "2_2") (pintype "input"))
      (node (ref "U10") (pin "3") (pinfunction "LX_3") (pintype "input"))
    )
    (net (code "81") (name "Net-(U11-MR#)") (class "Default")
      (node (ref "R23") (pin "1") (pinfunction "1_1") (pintype "input"))
      (node (ref "U11") (pin "3") (pinfunction "MR#_3") (pintype "input"))
    )
    (net (code "82") (name "Net-(USB2-CC1)") (class "Default")
      (node (ref "R8") (pin "2") (pinfunction "2_2") (pintype "input"))
      (node (ref "USB2") (pin "4") (pinfunction "CC1_4") (pintype "input"))
    )
    (net (code "83") (name "Net-(USB2-CC2)") (class "Default")
      (node (ref "R9") (pin "2") (pinfunction "2_2") (pintype "input"))
      (node (ref "USB2") (pin "10") (pinfunction "CC2_10") (pintype "input"))
    )
    (net (code "84") (name "unconnected-(CN1-Pad8)") (class "Default")
      (node (ref "CN1") (pin "8") (pinfunction "8_8") (pintype "input"))
    )
    (net (code "85") (name "unconnected-(CN1-Pad9)") (class "Default")
      (node (ref "CN1") (pin "9") (pinfunction "9_9") (pintype "input"))
    )
    (net (code "86") (name "unconnected-(U1-CLKOUT0{slash}GPH13-PadV8)") (class "Default")
      (node (ref "U1") (pin "V8") (pinfunction "CLKOUT0/GPH13_V8") (pintype "input"))
    )
    (net (code "87") (name "unconnected-(U1-CLKOUT1{slash}GPH14-PadY7)") (class "Default")
      (node (ref "U1") (pin "Y7") (pinfunction "CLKOUT1/GPH14_Y7") (pintype "input+no_connect"))
    )
    (net (code "88") (name "unconnected-(U1-DQM2{slash}GPA25-PadB16)") (class "Default")
      (node (ref "U1") (pin "B16") (pinfunction "DQM2/GPA25_B16") (pintype "input+no_connect"))
    )
    (net (code "89") (name "unconnected-(U1-DQM3{slash}GPA26-PadD14)") (class "Default")
      (node (ref "U1") (pin "D14") (pinfunction "DQM3/GPA26_D14") (pintype "input+no_connect"))
    )
    (net (code "90") (name "unconnected-(U1-PWR_EN-PadM15)") (class "Default")
      (node (ref "U1") (pin "M15") (pinfunction "PWR_EN_M15") (pintype "input+no_connect"))
    )
    (net (code "91") (name "unconnected-(U1-RADDR0{slash}GPA0-PadB3)") (class "Default")
      (node (ref "U1") (pin "B3") (pinfunction "RADDR0/GPA0_B3") (pintype "input+no_connect"))
    )
    (net (code "92") (name "unconnected-(U1-RADDR1-PadD7)") (class "Default")
      (node (ref "U1") (pin "D7") (pinfunction "RADDR1_D7") (pintype "input+no_connect"))
    )
    (net (code "93") (name "unconnected-(U1-RADDR2-PadA3)") (class "Default")
      (node (ref "U1") (pin "A3") (pinfunction "RADDR2_A3") (pintype "input+no_connect"))
    )
    (net (code "94") (name "unconnected-(U1-RADDR3-PadH8)") (class "Default")
      (node (ref "U1") (pin "H8") (pinfunction "RADDR3_H8") (pintype "input+no_connect"))
    )
    (net (code "95") (name "unconnected-(U1-RADDR4-PadC4)") (class "Default")
      (node (ref "U1") (pin "C4") (pinfunction "RADDR4_C4") (pintype "input+no_connect"))
    )
    (net (code "96") (name "unconnected-(U1-RADDR5-PadG8)") (class "Default")
      (node (ref "U1") (pin "G8") (pinfunction "RADDR5_G8") (pintype "input+no_connect"))
    )
    (net (code "97") (name "unconnected-(U1-RADDR6-PadB4)") (class "Default")
      (node (ref "U1") (pin "B4") (pinfunction "RADDR6_B4") (pintype "input+no_connect"))
    )
    (net (code "98") (name "unconnected-(U1-RADDR7-PadF8)") (class "Default")
      (node (ref "U1") (pin "F8") (pinfunction "RADDR7_F8") (pintype "input+no_connect"))
    )
    (net (code "99") (name "unconnected-(U1-RADDR8-PadA4)") (class "Default")
      (node (ref "U1") (pin "A4") (pinfunction "RADDR8_A4") (pintype "input+no_connect"))
    )
    (net (code "100") (name "unconnected-(U1-RADDR9-PadD8)") (class "Default")
      (node (ref "U1") (pin "D8") (pinfunction "RADDR9_D8") (pintype "input+no_connect"))
    )
    (net (code "101") (name "unconnected-(U1-RADDR10-PadA5)") (class "Default")
      (node (ref "U1") (pin "A5") (pinfunction "RADDR10_A5") (pintype "input+no_connect"))
    )
    (net (code "102") (name "unconnected-(U1-RADDR11-PadH9)") (class "Default")
      (node (ref "U1") (pin "H9") (pinfunction "RADDR11_H9") (pintype "input+no_connect"))
    )
    (net (code "103") (name "unconnected-(U1-RADDR12-PadC6)") (class "Default")
      (node (ref "U1") (pin "C6") (pinfunction "RADDR12_C6") (pintype "input+no_connect"))
    )
    (net (code "104") (name "unconnected-(U1-RADDR13-PadG9)") (class "Default")
      (node (ref "U1") (pin "G9") (pinfunction "RADDR13_G9") (pintype "input+no_connect"))
    )
    (net (code "105") (name "unconnected-(U1-RADDR14-PadB6)") (class "Default")
      (node (ref "U1") (pin "B6") (pinfunction "RADDR14_B6") (pintype "input+no_connect"))
    )
    (net (code "106") (name "unconnected-(U1-RADDR15-PadF9)") (class "Default")
      (node (ref "U1") (pin "F9") (pinfunction "RADDR15_F9") (pintype "input+no_connect"))
    )
    (net (code "107") (name "unconnected-(U1-RADDR16{slash}GPA1-PadA6)") (class "Default")
      (node (ref "U1") (pin "A6") (pinfunction "RADDR16/GPA1_A6") (pintype "input+no_connect"))
    )
    (net (code "108") (name "unconnected-(U1-RADDR17{slash}GPA2-PadD9)") (class "Default")
      (node (ref "U1") (pin "D9") (pinfunction "RADDR17/GPA2_D9") (pintype "input+no_connect"))
    )
    (net (code "109") (name "unconnected-(U1-RADDR18{slash}GPA3-PadC7)") (class "Default")
      (node (ref "U1") (pin "C7") (pinfunction "RADDR18/GPA3_C7") (pintype "input+no_connect"))
    )
    (net (code "110") (name "unconnected-(U1-RADDR19{slash}GPA4-PadC9)") (class "Default")
      (node (ref "U1") (pin "C9") (pinfunction "RADDR19/GPA4_C9") (pintype "input+no_connect"))
    )
    (net (code "111") (name "unconnected-(U1-RADDR20{slash}GPA5-PadB7)") (class "Default")
      (node (ref "U1") (pin "B7") (pinfunction "RADDR20/GPA5_B7") (pintype "input+no_connect"))
    )
    (net (code "112") (name "unconnected-(U1-RADDR21{slash}GPA6-PadH10)") (class "Default")
      (node (ref "U1") (pin "H10") (pinfunction "RADDR21/GPA6_H10") (pintype "input+no_connect"))
    )
    (net (code "113") (name "unconnected-(U1-RADDR22{slash}GPA7-PadA7)") (class "Default")
      (node (ref "U1") (pin "A7") (pinfunction "RADDR22/GPA7_A7") (pintype "input+no_connect"))
    )
    (net (code "114") (name "unconnected-(U1-RADDR23{slash}GPA8-PadG10)") (class "Default")
      (node (ref "U1") (pin "G10") (pinfunction "RADDR23/GPA8_G10") (pintype "input+no_connect"))
    )
    (net (code "115") (name "unconnected-(U1-RADDR24{slash}GPA9-PadC8)") (class "Default")
      (node (ref "U1") (pin "C8") (pinfunction "RADDR24/GPA9_C8") (pintype "input+no_connect"))
    )
    (net (code "116") (name "unconnected-(U1-RADDR25{slash}RDATA_OEN-PadF10)") (class "Default")
      (node (ref "U1") (pin "F10") (pinfunction "RADDR25/RDATA_OEN_F10") (pintype "input+no_connect"))
    )
    (net (code "117") (name "unconnected-(U1-RDATA0-PadH2)") (class "Default")
      (node (ref "U1") (pin "H2") (pinfunction "RDATA0_H2") (pintype "input"))
    )
    (net (code "118") (name "unconnected-(U1-RDATA1-PadK6)") (class "Default")
      (node (ref "U1") (pin "K6") (pinfunction "RDATA1_K6") (pintype "input"))
    )
    (net (code "119") (name "unconnected-(U1-RDATA2-PadH3)") (class "Default")
      (node (ref "U1") (pin "H3") (pinfunction "RDATA2_H3") (pintype "input"))
    )
    (net (code "120") (name "unconnected-(U1-RDATA3-PadL7)") (class "Default")
      (node (ref "U1") (pin "L7") (pinfunction "RDATA3_L7") (pintype "input"))
    )
    (net (code "121") (name "unconnected-(U1-RDATA4-PadG1)") (class "Default")
      (node (ref "U1") (pin "G1") (pinfunction "RDATA4_G1") (pintype "input"))
    )
    (net (code "122") (name "unconnected-(U1-RDATA5-PadK7)") (class "Default")
      (node (ref "U1") (pin "K7") (pinfunction "RDATA5_K7") (pintype "input"))
    )
    (net (code "123") (name "unconnected-(U1-RDATA6-PadG2)") (class "Default")
      (node (ref "U1") (pin "G2") (pinfunction "RDATA6_G2") (pintype "input"))
    )
    (net (code "124") (name "unconnected-(U1-RDATA7-PadK8)") (class "Default")
      (node (ref "U1") (pin "K8") (pinfunction "RDATA7_K8") (pintype "input"))
    )
    (net (code "125") (name "unconnected-(U1-RDATA8-PadG3)") (class "Default")
      (node (ref "U1") (pin "G3") (pinfunction "RDATA8_G3") (pintype "input+no_connect"))
    )
    (net (code "126") (name "unconnected-(U1-RDATA9-PadK4)") (class "Default")
      (node (ref "U1") (pin "K4") (pinfunction "RDATA9_K4") (pintype "input+no_connect"))
    )
    (net (code "127") (name "unconnected-(U1-RDATA10-PadF1)") (class "Default")
      (node (ref "U1") (pin "F1") (pinfunction "RDATA10_F1") (pintype "input+no_connect"))
    )
    (net (code "128") (name "unconnected-(U1-RDATA11-PadJ6)") (class "Default")
      (node (ref "U1") (pin "J6") (pinfunction "RDATA11_J6") (pintype "input+no_connect"))
    )
    (net (code "129") (name "unconnected-(U1-RDATA12-PadF2)") (class "Default")
      (node (ref "U1") (pin "F2") (pinfunction "RDATA12_F2") (pintype "input+no_connect"))
    )
    (net (code "130") (name "unconnected-(U1-RDATA13-PadJ4)") (class "Default")
      (node (ref "U1") (pin "J4") (pinfunction "RDATA13_J4") (pintype "input+no_connect"))
    )
    (net (code "131") (name "unconnected-(U1-RDATA14-PadE1)") (class "Default")
      (node (ref "U1") (pin "E1") (pinfunction "RDATA14_E1") (pintype "input+no_connect"))
    )
    (net (code "132") (name "unconnected-(U1-RDATA15-PadH7)") (class "Default")
      (node (ref "U1") (pin "H7") (pinfunction "RDATA15_H7") (pintype "input+no_connect"))
    )
    (net (code "133") (name "unconnected-(U1-RSMBWAIT{slash}GPM0-PadC2)") (class "Default")
      (node (ref "U1") (pin "C2") (pinfunction "RSMBWAIT/GPM0_C2") (pintype "input+no_connect"))
    )
    (net (code "134") (name "unconnected-(U1-RSMCLK{slash}GPA23-PadB1)") (class "Default")
      (node (ref "U1") (pin "B1") (pinfunction "RSMCLK/GPA23_B1") (pintype "input+no_connect"))
    )
    (net (code "135") (name "unconnected-(U1-RSMVAD{slash}GPA24-PadE4)") (class "Default")
      (node (ref "U1") (pin "E4") (pinfunction "RSMVAD/GPA24_E4") (pintype "input+no_connect"))
    )
    (net (code "136") (name "unconnected-(U1-SADDR13-PadA9)") (class "Default")
      (node (ref "U1") (pin "A9") (pinfunction "SADDR13_A9") (pintype "input+no_connect"))
    )
    (net (code "137") (name "unconnected-(U1-SDATA16{slash}GPK0-PadD20)") (class "Default")
      (node (ref "U1") (pin "D20") (pinfunction "SDATA16/GPK0_D20") (pintype "input+no_connect"))
    )
    (net (code "138") (name "unconnected-(U1-SDATA17{slash}GPK1-PadF17)") (class "Default")
      (node (ref "U1") (pin "F17") (pinfunction "SDATA17/GPK1_F17") (pintype "input+no_connect"))
    )
    (net (code "139") (name "unconnected-(U1-SDATA18{slash}GPK2-PadE18)") (class "Default")
      (node (ref "U1") (pin "E18") (pinfunction "SDATA18/GPK2_E18") (pintype "input+no_connect"))
    )
    (net (code "140") (name "unconnected-(U1-SDATA19{slash}GPK3-PadG15)") (class "Default")
      (node (ref "U1") (pin "G15") (pinfunction "SDATA19/GPK3_G15") (pintype "input+no_connect"))
    )
    (net (code "141") (name "unconnected-(U1-SDATA20{slash}GPK4-PadE19)") (class "Default")
      (node (ref "U1") (pin "E19") (pinfunction "SDATA20/GPK4_E19") (pintype "input+no_connect"))
    )
    (net (code "142") (name "unconnected-(U1-SDATA21{slash}GPK5-PadG17)") (class "Default")
      (node (ref "U1") (pin "G17") (pinfunction "SDATA21/GPK5_G17") (pintype "input+no_connect"))
    )
    (net (code "143") (name "unconnected-(U1-SDATA22{slash}GPK6-PadE20)") (class "Default")
      (node (ref "U1") (pin "E20") (pinfunction "SDATA22/GPK6_E20") (pintype "input+no_connect"))
    )
    (net (code "144") (name "unconnected-(U1-SDATA23{slash}GPK7-PadH15)") (class "Default")
      (node (ref "U1") (pin "H15") (pinfunction "SDATA23/GPK7_H15") (pintype "input+no_connect"))
    )
    (net (code "145") (name "unconnected-(U1-SDATA24{slash}GPK8-PadF18)") (class "Default")
      (node (ref "U1") (pin "F18") (pinfunction "SDATA24/GPK8_F18") (pintype "input+no_connect"))
    )
    (net (code "146") (name "unconnected-(U1-SDATA25{slash}GPK9-PadH17)") (class "Default")
      (node (ref "U1") (pin "H17") (pinfunction "SDATA25/GPK9_H17") (pintype "input+no_connect"))
    )
    (net (code "147") (name "unconnected-(U1-SDATA26{slash}GPK10-PadF19)") (class "Default")
      (node (ref "U1") (pin "F19") (pinfunction "SDATA26/GPK10_F19") (pintype "input+no_connect"))
    )
    (net (code "148") (name "unconnected-(U1-SDATA27{slash}GPK11-PadJ14)") (class "Default")
      (node (ref "U1") (pin "J14") (pinfunction "SDATA27/GPK11_J14") (pintype "input+no_connect"))
    )
    (net (code "149") (name "unconnected-(U1-SDATA28{slash}GPK12-PadF20)") (class "Default")
      (node (ref "U1") (pin "F20") (pinfunction "SDATA28/GPK12_F20") (pintype "input+no_connect"))
    )
    (net (code "150") (name "unconnected-(U1-SDATA29{slash}GPK13-PadJ15)") (class "Default")
      (node (ref "U1") (pin "J15") (pinfunction "SDATA29/GPK13_J15") (pintype "input+no_connect"))
    )
    (net (code "151") (name "unconnected-(U1-SDATA30{slash}GPK14-PadG20)") (class "Default")
      (node (ref "U1") (pin "G20") (pinfunction "SDATA30/GPK14_G20") (pintype "input+no_connect"))
    )
    (net (code "152") (name "unconnected-(U1-SDATA31{slash}GPK15-PadJ18)") (class "Default")
      (node (ref "U1") (pin "J18") (pinfunction "SDATA31/GPK15_J18") (pintype "input+no_connect"))
    )
    (net (code "153") (name "unconnected-(U1-TOUT3{slash}GPB3-PadW1)") (class "Default")
      (node (ref "U1") (pin "W1") (pinfunction "TOUT3/GPB3_W1") (pintype "input+no_connect"))
    )
    (net (code "154") (name "unconnected-(U1-XTOrtc-PadT17)") (class "Default")
      (node (ref "U1") (pin "T17") (pinfunction "XTOrtc_T17") (pintype "output+no_connect"))
    )
    (net (code "155") (name "unconnected-(U1-nRBE0-PadC3)") (class "Default")
      (node (ref "U1") (pin "C3") (pinfunction "nRBE0_C3") (pintype "input+no_connect"))
    )
    (net (code "156") (name "unconnected-(U1-nRBE1-PadF7)") (class "Default")
      (node (ref "U1") (pin "F7") (pinfunction "nRBE1_F7") (pintype "input+no_connect"))
    )
    (net (code "157") (name "unconnected-(U1-nRCS0-PadD5)") (class "Default")
      (node (ref "U1") (pin "D5") (pinfunction "nRCS0_D5") (pintype "input+no_connect"))
    )
    (net (code "158") (name "unconnected-(U1-nRCS1{slash}GPA12-PadB2)") (class "Default")
      (node (ref "U1") (pin "B2") (pinfunction "nRCS1/GPA12_B2") (pintype "input+no_connect"))
    )
    (net (code "159") (name "unconnected-(U1-nRCS2{slash}GPA13-PadD4)") (class "Default")
      (node (ref "U1") (pin "D4") (pinfunction "nRCS2/GPA13_D4") (pintype "input+no_connect"))
    )
    (net (code "160") (name "unconnected-(U1-nRCS3{slash}GPA14-PadF4)") (class "Default")
      (node (ref "U1") (pin "F4") (pinfunction "nRCS3/GPA14_F4") (pintype "input+no_connect"))
    )
    (net (code "161") (name "unconnected-(U1-nRCS4{slash}GPA15-PadC1)") (class "Default")
      (node (ref "U1") (pin "C1") (pinfunction "nRCS4/GPA15_C1") (pintype "input+no_connect"))
    )
    (net (code "162") (name "unconnected-(U1-nRCS5{slash}GPA16-PadG6)") (class "Default")
      (node (ref "U1") (pin "G6") (pinfunction "nRCS5/GPA16_G6") (pintype "input+no_connect"))
    )
    (net (code "163") (name "unconnected-(U1-nROE-PadD6)") (class "Default")
      (node (ref "U1") (pin "D6") (pinfunction "nROE_D6") (pintype "input+no_connect"))
    )
    (net (code "164") (name "unconnected-(U1-nRSTOUT{slash}GPA21-PadN18)") (class "Default")
      (node (ref "U1") (pin "N18") (pinfunction "nRSTOUT/GPA21_N18") (pintype "input+no_connect"))
    )
    (net (code "165") (name "unconnected-(U1-nRWE-PadA2)") (class "Default")
      (node (ref "U1") (pin "A2") (pinfunction "nRWE_A2") (pintype "input+no_connect"))
    )
    (net (code "166") (name "unconnected-(U1-nSCS1-PadB15)") (class "Default")
      (node (ref "U1") (pin "B15") (pinfunction "nSCS1_B15") (pintype "input+no_connect"))
    )
    (net (code "167") (name "unconnected-(U1-nXBACK{slash}GPB5-PadU6)") (class "Default")
      (node (ref "U1") (pin "U6") (pinfunction "nXBACK/GPB5_U6") (pintype "input+no_connect"))
    )
    (net (code "168") (name "unconnected-(U1-nXBREQ{slash}RTCK{slash}GPB6-PadV4)") (class "Default")
      (node (ref "U1") (pin "V4") (pinfunction "nXBREQ/RTCK/GPB6_V4") (pintype "input+no_connect"))
    )
    (net (code "169") (name "unconnected-(U1-nXDACK0{slash}I2S0_SDO1{slash}GPB9-PadW4)") (class "Default")
      (node (ref "U1") (pin "W4") (pinfunction "nXDACK0/I2S0_SDO1/GPB9_W4") (pintype "input+no_connect"))
    )
    (net (code "170") (name "unconnected-(U1-nXDREQ0{slash}I2S0_SDO2{slash}GPB10-PadU5)") (class "Default")
      (node (ref "U1") (pin "U5") (pinfunction "nXDREQ0/I2S0_SDO2/GPB10_U5") (pintype "input+no_connect"))
    )
    (net (code "171") (name "unconnected-(U4-LDQS#-PadE8)") (class "Default")
      (node (ref "U4") (pin "E8") (pinfunction "LDQS#_E8") (pintype "input+no_connect"))
    )
    (net (code "172") (name "unconnected-(U4-NC-PadA2)") (class "Default")
      (node (ref "U4") (pin "A2") (pinfunction "NC_A2") (pintype "input+no_connect"))
    )
    (net (code "173") (name "unconnected-(U4-NC-PadE2)") (class "Default")
      (node (ref "U4") (pin "E2") (pinfunction "NC_E2") (pintype "input+no_connect"))
    )
    (net (code "174") (name "unconnected-(U4-NC-PadR3)") (class "Default")
      (node (ref "U4") (pin "R3") (pinfunction "NC_R3") (pintype "input+no_connect"))
    )
    (net (code "175") (name "unconnected-(U4-NC-PadR7)") (class "Default")
      (node (ref "U4") (pin "R7") (pinfunction "NC_R7") (pintype "input+no_connect"))
    )
    (net (code "176") (name "unconnected-(U4-NC-PadR8)") (class "Default")
      (node (ref "U4") (pin "R8") (pinfunction "NC_R8") (pintype "input+no_connect"))
    )
    (net (code "177") (name "unconnected-(U4-UDQS#-PadA8)") (class "Default")
      (node (ref "U4") (pin "A8") (pinfunction "UDQS#_A8") (pintype "input+no_connect"))
    )
    (net (code "178") (name "unconnected-(USB2-SBU1-Pad9)") (class "Default")
      (node (ref "USB2") (pin "9") (pinfunction "SBU1_9") (pintype "input"))
    )
    (net (code "179") (name "unconnected-(USB2-SBU2-Pad3)") (class "Default")
      (node (ref "USB2") (pin "3") (pinfunction "SBU2_3") (pintype "input"))
    )
  )
)
